# 01_fpga.net
KiCad netlist of a schematic drawn in Altium Designer
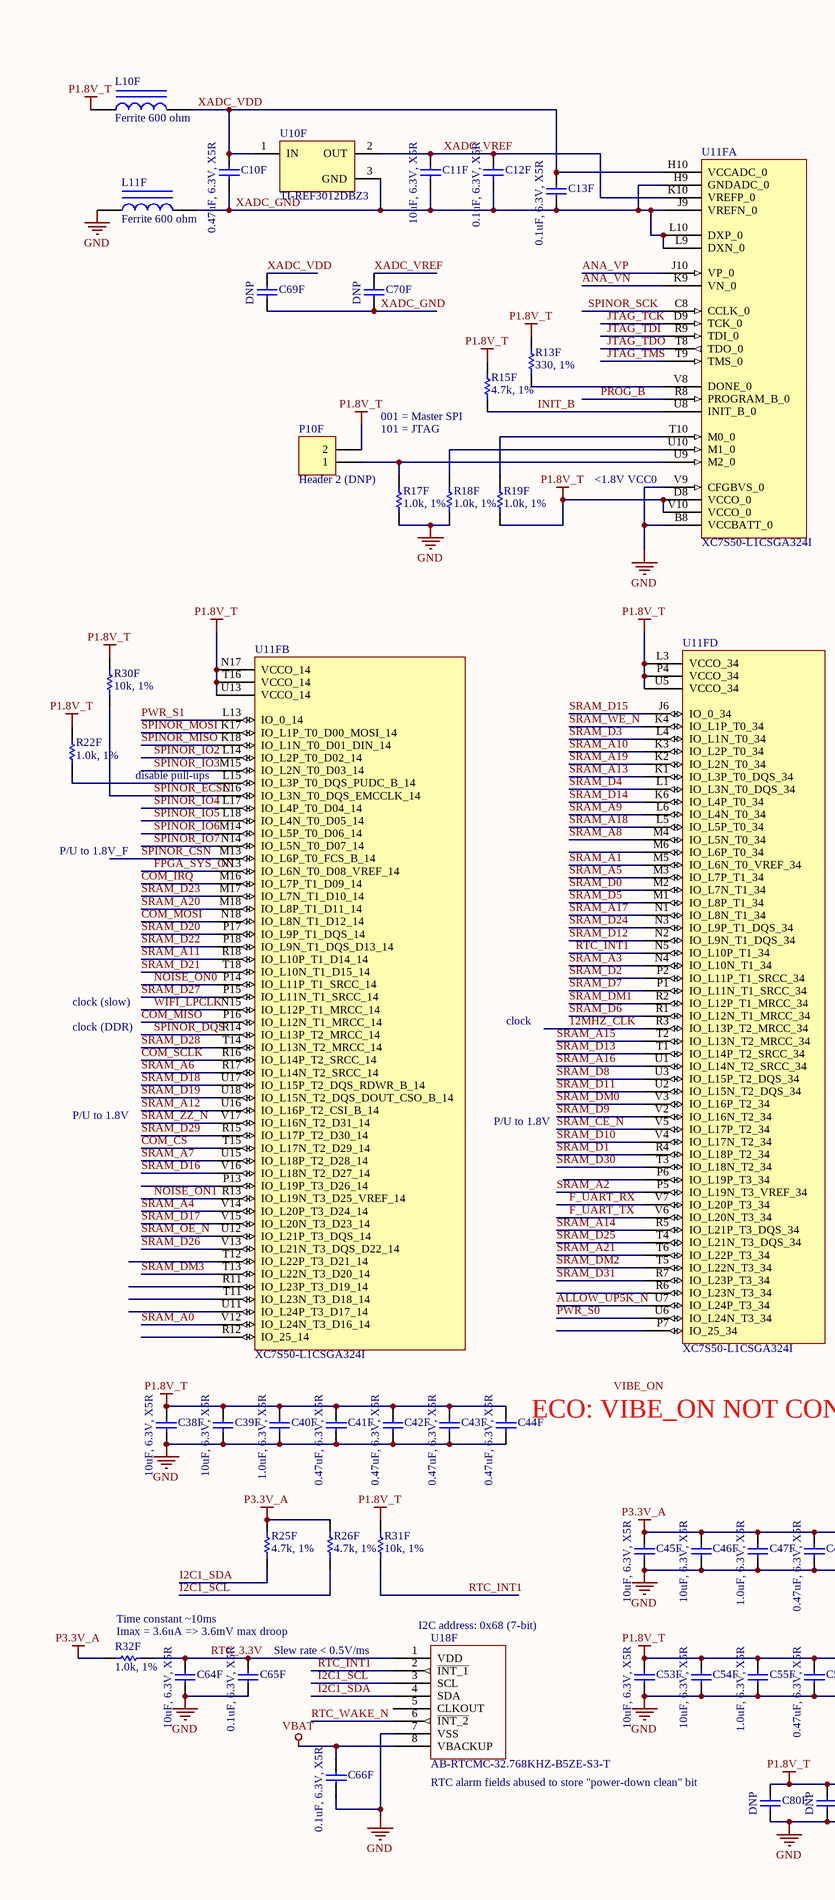
[diagram p0: 01_fpga.SchDoc, left]
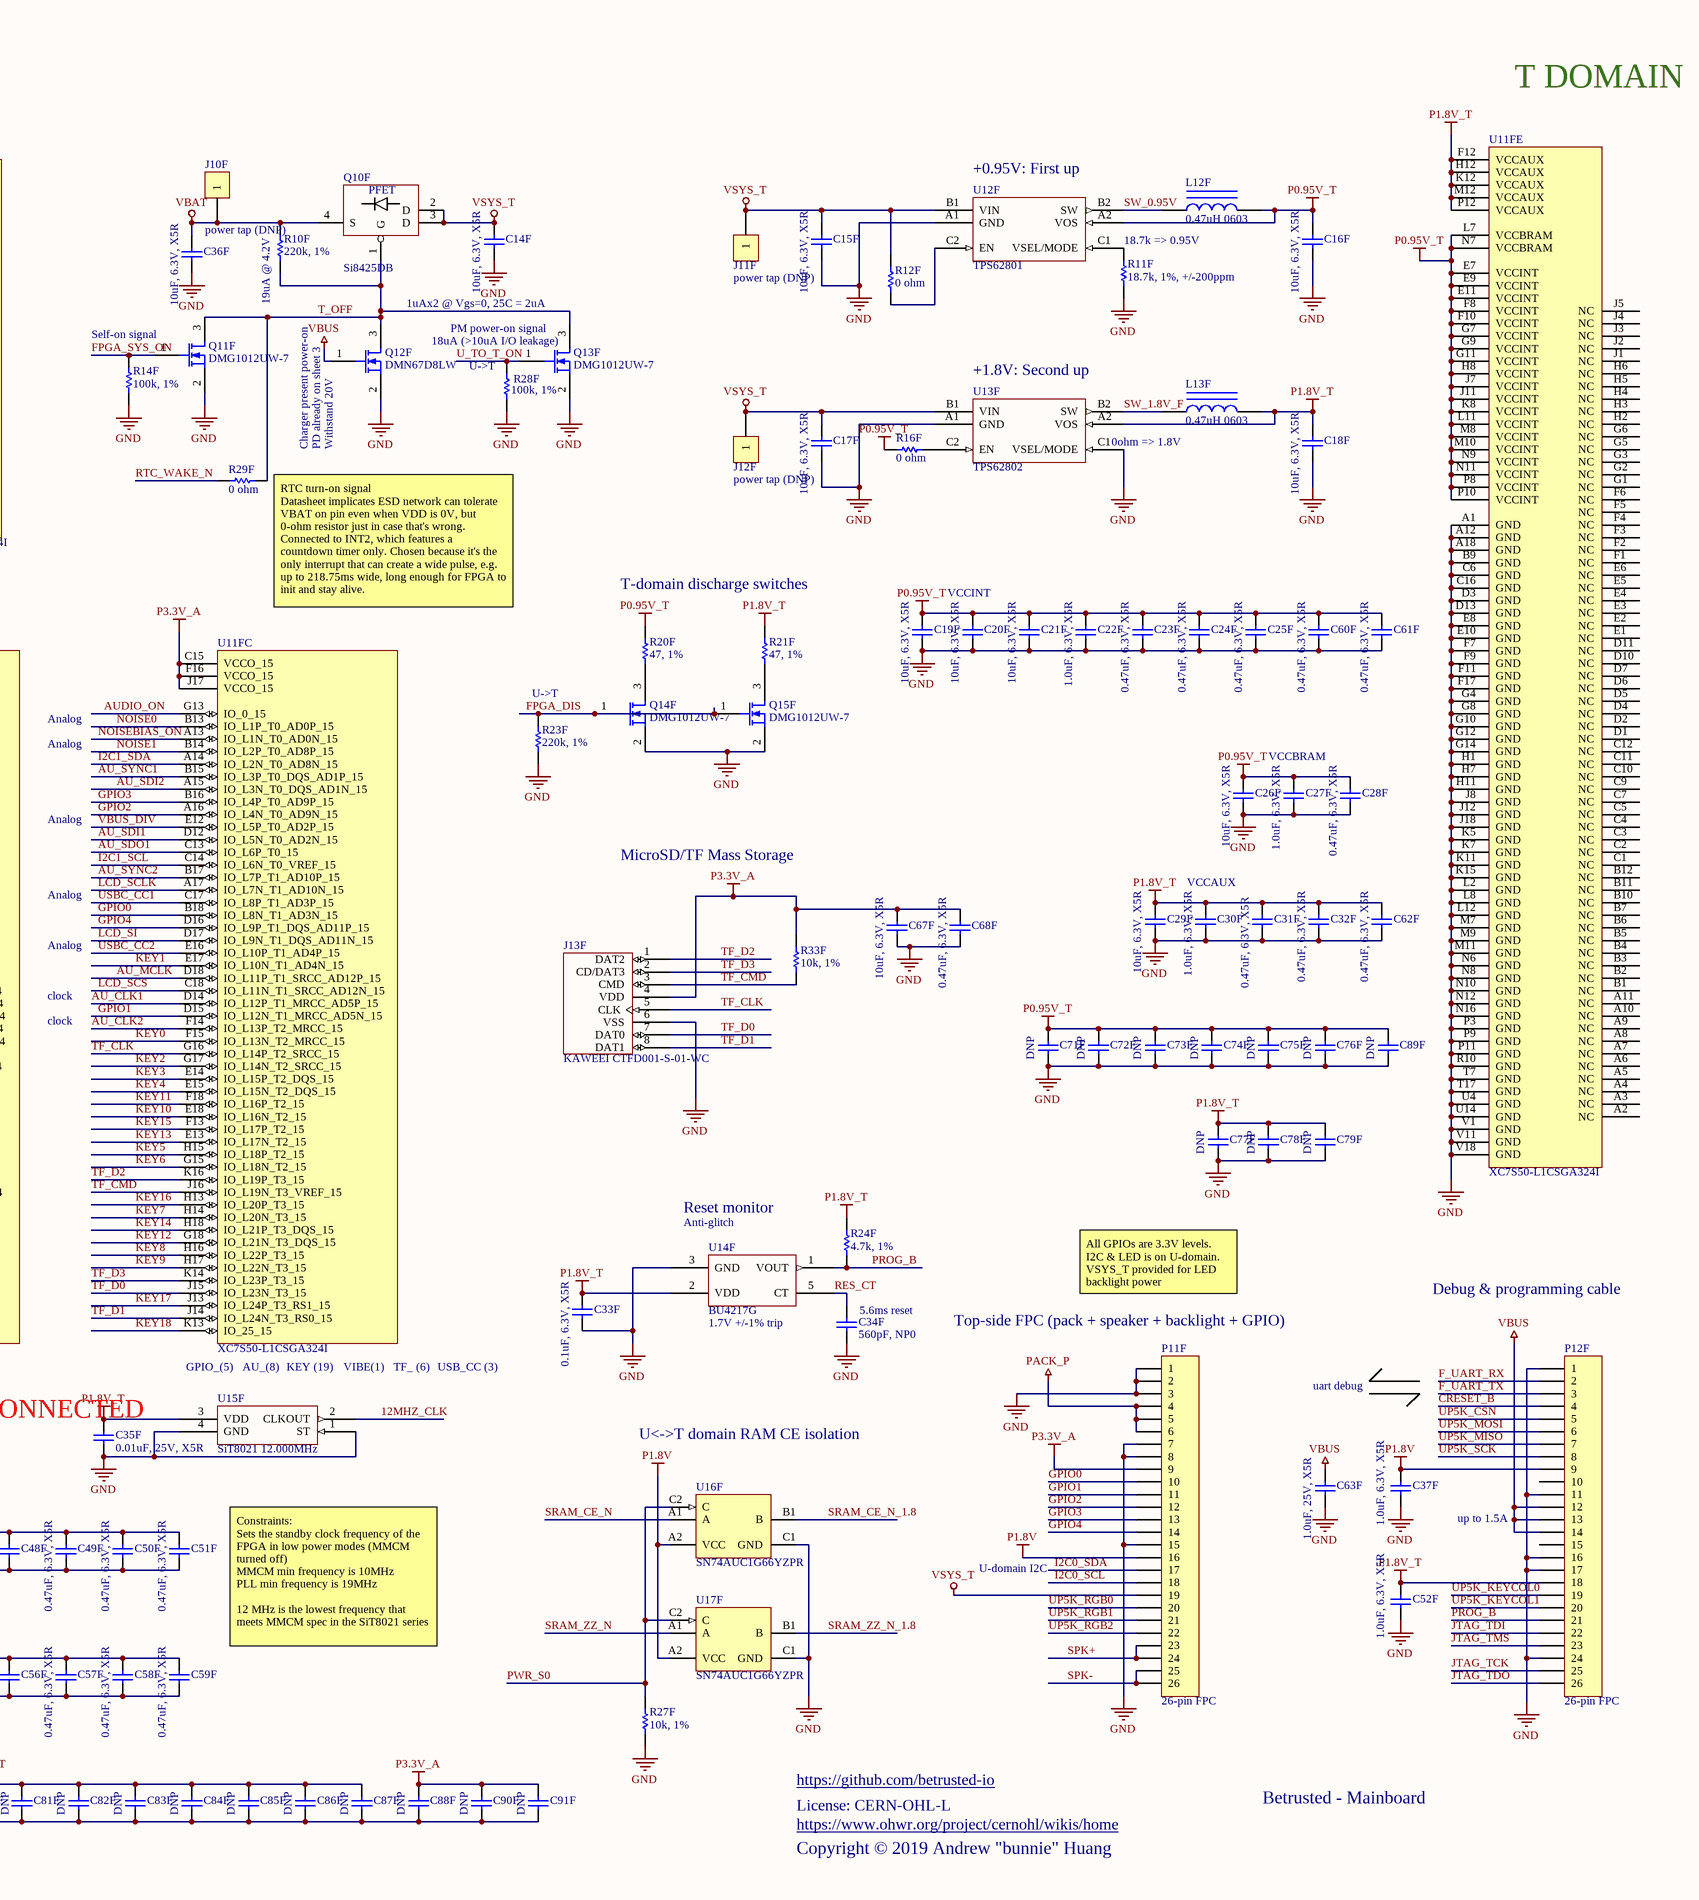
[diagram p1: 01_fpga.SchDoc, right]

(export (version "E")
  (design (tool "Eeschema 10.0.6"))
  (components
    (comp (ref "C10F")
      (value "0.47uF, 6.3V, X5R")
      (footprint "B_CAP0201")
      (description "Capacitor (Semiconductor SIM Model)")
      (fields (field (name "MPN") "CL03A474KQ3NNNH"))
      (libsource (lib "Miscellaneous Devices") (part "Cap Semi"))
    )
    (comp (ref "C11F")
      (value "10uF, 6.3V, X5R")
      (footprint "B_CAP0603")
      (description "Capacitor (Semiconductor SIM Model)")
      (fields (field (name "MPN") "CL10A106MQ8NNNC"))
      (libsource (lib "Miscellaneous Devices") (part "Cap Semi"))
    )
    (comp (ref "C12F")
      (value "0.1uF, 6.3V, X5R")
      (footprint "B_CAP0201")
      (description "Capacitor (Semiconductor SIM Model)")
      (fields (field (name "MPN") "CL03A104KQ3NNNC"))
      (libsource (lib "Miscellaneous Devices") (part "Cap Semi"))
    )
    (comp (ref "C13F")
      (value "0.1uF, 6.3V, X5R")
      (footprint "B_CAP0201")
      (description "Capacitor (Semiconductor SIM Model)")
      (fields (field (name "MPN") "CL03A104KQ3NNNC"))
      (libsource (lib "Miscellaneous Devices") (part "Cap Semi"))
    )
    (comp (ref "C14F")
      (value "10uF, 6.3V, X5R")
      (footprint "B_CAP0603")
      (description "Capacitor (Semiconductor SIM Model)")
      (fields (field (name "MPN") "CL10A106MQ8NNNC"))
      (libsource (lib "Miscellaneous Devices") (part "Cap Semi"))
    )
    (comp (ref "C15F")
      (value "10uF, 6.3V, X5R")
      (footprint "B_CAP0603")
      (description "Capacitor (Semiconductor SIM Model)")
      (fields (field (name "MPN") "CL10A106MQ8NNNC"))
      (libsource (lib "Miscellaneous Devices") (part "Cap Semi"))
    )
    (comp (ref "C16F")
      (value "10uF, 6.3V, X5R")
      (footprint "B_CAP0603")
      (description "Capacitor (Semiconductor SIM Model)")
      (fields (field (name "MPN") "CL10A106MQ8NNNC"))
      (libsource (lib "Miscellaneous Devices") (part "Cap Semi"))
    )
    (comp (ref "C17F")
      (value "10uF, 6.3V, X5R")
      (footprint "B_CAP0603")
      (description "Capacitor (Semiconductor SIM Model)")
      (fields (field (name "MPN") "CL10A106MQ8NNNC"))
      (libsource (lib "Miscellaneous Devices") (part "Cap Semi"))
    )
    (comp (ref "C18F")
      (value "10uF, 6.3V, X5R")
      (footprint "B_CAP0603")
      (description "Capacitor (Semiconductor SIM Model)")
      (fields (field (name "MPN") "CL10A106MQ8NNNC"))
      (libsource (lib "Miscellaneous Devices") (part "Cap Semi"))
    )
    (comp (ref "C19F")
      (value "10uF, 6.3V, X5R")
      (footprint "B_CAP0603")
      (description "Capacitor (Semiconductor SIM Model)")
      (fields (field (name "MPN") "CL10A106MQ8NNNC"))
      (libsource (lib "Miscellaneous Devices") (part "Cap Semi"))
    )
    (comp (ref "C20F")
      (value "10uF, 6.3V, X5R")
      (footprint "B_CAP0603")
      (description "Capacitor (Semiconductor SIM Model)")
      (fields (field (name "MPN") "CL10A106MQ8NNNC"))
      (libsource (lib "Miscellaneous Devices") (part "Cap Semi"))
    )
    (comp (ref "C21F")
      (value "10uF, 6.3V, X5R")
      (footprint "B_CAP0603")
      (description "Capacitor (Semiconductor SIM Model)")
      (fields (field (name "MPN") "CL10A106MQ8NNNC"))
      (libsource (lib "Miscellaneous Devices") (part "Cap Semi"))
    )
    (comp (ref "C22F")
      (value "1.0uF, 6.3V, X5R")
      (footprint "B_CAP0201")
      (description "Capacitor (Semiconductor SIM Model)")
      (fields (field (name "MPN") "GRM033R60J105MEA2D"))
      (libsource (lib "Miscellaneous Devices") (part "Cap Semi"))
    )
    (comp (ref "C23F")
      (value "0.47uF, 6.3V, X5R")
      (footprint "B_CAP0201")
      (description "Capacitor (Semiconductor SIM Model)")
      (fields (field (name "MPN") "CL03A474KQ3NNNH"))
      (libsource (lib "Miscellaneous Devices") (part "Cap Semi"))
    )
    (comp (ref "C24F")
      (value "0.47uF, 6.3V, X5R")
      (footprint "B_CAP0201")
      (description "Capacitor (Semiconductor SIM Model)")
      (fields (field (name "MPN") "CL03A474KQ3NNNH"))
      (libsource (lib "Miscellaneous Devices") (part "Cap Semi"))
    )
    (comp (ref "C25F")
      (value "0.47uF, 6.3V, X5R")
      (footprint "B_CAP0201")
      (description "Capacitor (Semiconductor SIM Model)")
      (fields (field (name "MPN") "CL03A474KQ3NNNH"))
      (libsource (lib "Miscellaneous Devices") (part "Cap Semi"))
    )
    (comp (ref "C26F")
      (value "10uF, 6.3V, X5R")
      (footprint "B_CAP0603")
      (description "Capacitor (Semiconductor SIM Model)")
      (fields (field (name "MPN") "CL10A106MQ8NNNC"))
      (libsource (lib "Miscellaneous Devices") (part "Cap Semi"))
    )
    (comp (ref "C27F")
      (value "1.0uF, 6.3V, X5R")
      (footprint "B_CAP0201")
      (description "Capacitor (Semiconductor SIM Model)")
      (fields (field (name "MPN") "GRM033R60J105MEA2D"))
      (libsource (lib "Miscellaneous Devices") (part "Cap Semi"))
    )
    (comp (ref "C28F")
      (value "0.47uF, 6.3V, X5R")
      (footprint "B_CAP0201")
      (description "Capacitor (Semiconductor SIM Model)")
      (fields (field (name "MPN") "CL03A474KQ3NNNH"))
      (libsource (lib "Miscellaneous Devices") (part "Cap Semi"))
    )
    (comp (ref "C29F")
      (value "10uF, 6.3V, X5R")
      (footprint "B_CAP0603")
      (description "Capacitor (Semiconductor SIM Model)")
      (fields (field (name "MPN") "CL10A106MQ8NNNC"))
      (libsource (lib "Miscellaneous Devices") (part "Cap Semi"))
    )
    (comp (ref "C30F")
      (value "1.0uF, 6.3V, X5R")
      (footprint "B_CAP0201")
      (description "Capacitor (Semiconductor SIM Model)")
      (fields (field (name "MPN") "GRM033R60J105MEA2D"))
      (libsource (lib "Miscellaneous Devices") (part "Cap Semi"))
    )
    (comp (ref "C31F")
      (value "0.47uF, 6.3V, X5R")
      (footprint "B_CAP0201")
      (description "Capacitor (Semiconductor SIM Model)")
      (fields (field (name "MPN") "CL03A474KQ3NNNH"))
      (libsource (lib "Miscellaneous Devices") (part "Cap Semi"))
    )
    (comp (ref "C32F")
      (value "0.47uF, 6.3V, X5R")
      (footprint "B_CAP0201")
      (description "Capacitor (Semiconductor SIM Model)")
      (fields (field (name "MPN") "CL03A474KQ3NNNH"))
      (libsource (lib "Miscellaneous Devices") (part "Cap Semi"))
    )
    (comp (ref "C33F")
      (value "0.1uF, 6.3V, X5R")
      (footprint "B_CAP0201")
      (description "Capacitor (Semiconductor SIM Model)")
      (fields (field (name "MPN") "CL03A104KQ3NNNC"))
      (libsource (lib "Miscellaneous Devices") (part "Cap Semi"))
    )
    (comp (ref "C34F")
      (value "560pF, NP0")
      (footprint "B_RES0201")
      (description "Capacitor (Semiconductor SIM Model)")
      (fields (field (name "MPN") "GRM0335C1E561JA01D"))
      (libsource (lib "Miscellaneous Devices") (part "Cap Semi"))
    )
    (comp (ref "C35F")
      (value "0.01uF, 25V, X5R")
      (footprint "B_RES0201")
      (description "Capacitor (Semiconductor SIM Model)")
      (fields (field (name "MPN") "GRM033R61E103KA12D"))
      (libsource (lib "Miscellaneous Devices") (part "Cap Semi"))
    )
    (comp (ref "C36F")
      (value "10uF, 6.3V, X5R")
      (footprint "B_CAP0603")
      (description "Capacitor (Semiconductor SIM Model)")
      (fields (field (name "MPN") "CL10A106MQ8NNNC"))
      (libsource (lib "Miscellaneous Devices") (part "Cap Semi"))
    )
    (comp (ref "C37F")
      (value "1.0uF, 6.3V, X5R")
      (footprint "B_CAP0201")
      (description "Capacitor (Semiconductor SIM Model)")
      (fields (field (name "MPN") "GRM033R60J105MEA2D"))
      (libsource (lib "Miscellaneous Devices") (part "Cap Semi"))
    )
    (comp (ref "C38F")
      (value "10uF, 6.3V, X5R")
      (footprint "B_CAP0603")
      (description "Capacitor (Semiconductor SIM Model)")
      (fields (field (name "MPN") "CL10A106MQ8NNNC"))
      (libsource (lib "Miscellaneous Devices") (part "Cap Semi"))
    )
    (comp (ref "C39F")
      (value "10uF, 6.3V, X5R")
      (footprint "B_CAP0603")
      (description "Capacitor (Semiconductor SIM Model)")
      (fields (field (name "MPN") "CL10A106MQ8NNNC"))
      (libsource (lib "Miscellaneous Devices") (part "Cap Semi"))
    )
    (comp (ref "C40F")
      (value "1.0uF, 6.3V, X5R")
      (footprint "B_CAP0201")
      (description "Capacitor (Semiconductor SIM Model)")
      (fields (field (name "MPN") "GRM033R60J105MEA2D"))
      (libsource (lib "Miscellaneous Devices") (part "Cap Semi"))
    )
    (comp (ref "C41F")
      (value "0.47uF, 6.3V, X5R")
      (footprint "B_CAP0201")
      (description "Capacitor (Semiconductor SIM Model)")
      (fields (field (name "MPN") "CL03A474KQ3NNNH"))
      (libsource (lib "Miscellaneous Devices") (part "Cap Semi"))
    )
    (comp (ref "C42F")
      (value "0.47uF, 6.3V, X5R")
      (footprint "B_CAP0201")
      (description "Capacitor (Semiconductor SIM Model)")
      (fields (field (name "MPN") "CL03A474KQ3NNNH"))
      (libsource (lib "Miscellaneous Devices") (part "Cap Semi"))
    )
    (comp (ref "C43F")
      (value "0.47uF, 6.3V, X5R")
      (footprint "B_CAP0201")
      (description "Capacitor (Semiconductor SIM Model)")
      (fields (field (name "MPN") "CL03A474KQ3NNNH"))
      (libsource (lib "Miscellaneous Devices") (part "Cap Semi"))
    )
    (comp (ref "C44F")
      (value "0.47uF, 6.3V, X5R")
      (footprint "B_CAP0201")
      (description "Capacitor (Semiconductor SIM Model)")
      (fields (field (name "MPN") "CL03A474KQ3NNNH"))
      (libsource (lib "Miscellaneous Devices") (part "Cap Semi"))
    )
    (comp (ref "C45F")
      (value "10uF, 6.3V, X5R")
      (footprint "B_CAP0603")
      (description "Capacitor (Semiconductor SIM Model)")
      (fields (field (name "MPN") "CL10A106MQ8NNNC"))
      (libsource (lib "Miscellaneous Devices") (part "Cap Semi"))
    )
    (comp (ref "C46F")
      (value "10uF, 6.3V, X5R")
      (footprint "B_CAP0603")
      (description "Capacitor (Semiconductor SIM Model)")
      (fields (field (name "MPN") "CL10A106MQ8NNNC"))
      (libsource (lib "Miscellaneous Devices") (part "Cap Semi"))
    )
    (comp (ref "C47F")
      (value "1.0uF, 6.3V, X5R")
      (footprint "B_CAP0201")
      (description "Capacitor (Semiconductor SIM Model)")
      (fields (field (name "MPN") "GRM033R60J105MEA2D"))
      (libsource (lib "Miscellaneous Devices") (part "Cap Semi"))
    )
    (comp (ref "C48F")
      (value "0.47uF, 6.3V, X5R")
      (footprint "B_CAP0201")
      (description "Capacitor (Semiconductor SIM Model)")
      (fields (field (name "MPN") "CL03A474KQ3NNNH"))
      (libsource (lib "Miscellaneous Devices") (part "Cap Semi"))
    )
    (comp (ref "C49F")
      (value "0.47uF, 6.3V, X5R")
      (footprint "B_CAP0201")
      (description "Capacitor (Semiconductor SIM Model)")
      (fields (field (name "MPN") "CL03A474KQ3NNNH"))
      (libsource (lib "Miscellaneous Devices") (part "Cap Semi"))
    )
    (comp (ref "C50F")
      (value "0.47uF, 6.3V, X5R")
      (footprint "B_CAP0201")
      (description "Capacitor (Semiconductor SIM Model)")
      (fields (field (name "MPN") "CL03A474KQ3NNNH"))
      (libsource (lib "Miscellaneous Devices") (part "Cap Semi"))
    )
    (comp (ref "C51F")
      (value "0.47uF, 6.3V, X5R")
      (footprint "B_CAP0201")
      (description "Capacitor (Semiconductor SIM Model)")
      (fields (field (name "MPN") "CL03A474KQ3NNNH"))
      (libsource (lib "Miscellaneous Devices") (part "Cap Semi"))
    )
    (comp (ref "C52F")
      (value "1.0uF, 6.3V, X5R")
      (footprint "B_CAP0201")
      (description "Capacitor (Semiconductor SIM Model)")
      (fields (field (name "MPN") "GRM033R60J105MEA2D"))
      (libsource (lib "Miscellaneous Devices") (part "Cap Semi"))
    )
    (comp (ref "C53F")
      (value "10uF, 6.3V, X5R")
      (footprint "B_CAP0603")
      (description "Capacitor (Semiconductor SIM Model)")
      (fields (field (name "MPN") "CL10A106MQ8NNNC"))
      (libsource (lib "Miscellaneous Devices") (part "Cap Semi"))
    )
    (comp (ref "C54F")
      (value "10uF, 6.3V, X5R")
      (footprint "B_CAP0603")
      (description "Capacitor (Semiconductor SIM Model)")
      (fields (field (name "MPN") "CL10A106MQ8NNNC"))
      (libsource (lib "Miscellaneous Devices") (part "Cap Semi"))
    )
    (comp (ref "C55F")
      (value "1.0uF, 6.3V, X5R")
      (footprint "B_CAP0201")
      (description "Capacitor (Semiconductor SIM Model)")
      (fields (field (name "MPN") "GRM033R60J105MEA2D"))
      (libsource (lib "Miscellaneous Devices") (part "Cap Semi"))
    )
    (comp (ref "C56F")
      (value "0.47uF, 6.3V, X5R")
      (footprint "B_CAP0201")
      (description "Capacitor (Semiconductor SIM Model)")
      (fields (field (name "MPN") "CL03A474KQ3NNNH"))
      (libsource (lib "Miscellaneous Devices") (part "Cap Semi"))
    )
    (comp (ref "C57F")
      (value "0.47uF, 6.3V, X5R")
      (footprint "B_CAP0201")
      (description "Capacitor (Semiconductor SIM Model)")
      (fields (field (name "MPN") "CL03A474KQ3NNNH"))
      (libsource (lib "Miscellaneous Devices") (part "Cap Semi"))
    )
    (comp (ref "C58F")
      (value "0.47uF, 6.3V, X5R")
      (footprint "B_CAP0201")
      (description "Capacitor (Semiconductor SIM Model)")
      (fields (field (name "MPN") "CL03A474KQ3NNNH"))
      (libsource (lib "Miscellaneous Devices") (part "Cap Semi"))
    )
    (comp (ref "C59F")
      (value "0.47uF, 6.3V, X5R")
      (footprint "B_CAP0201")
      (description "Capacitor (Semiconductor SIM Model)")
      (fields (field (name "MPN") "CL03A474KQ3NNNH"))
      (libsource (lib "Miscellaneous Devices") (part "Cap Semi"))
    )
    (comp (ref "C60F")
      (value "0.47uF, 6.3V, X5R")
      (footprint "B_CAP0201")
      (description "Capacitor (Semiconductor SIM Model)")
      (fields (field (name "MPN") "CL03A474KQ3NNNH"))
      (libsource (lib "Miscellaneous Devices") (part "Cap Semi"))
    )
    (comp (ref "C61F")
      (value "0.47uF, 6.3V, X5R")
      (footprint "B_CAP0201")
      (description "Capacitor (Semiconductor SIM Model)")
      (fields (field (name "MPN") "CL03A474KQ3NNNH"))
      (libsource (lib "Miscellaneous Devices") (part "Cap Semi"))
    )
    (comp (ref "C62F")
      (value "0.47uF, 6.3V, X5R")
      (footprint "B_CAP0201")
      (description "Capacitor (Semiconductor SIM Model)")
      (fields (field (name "MPN") "CL03A474KQ3NNNH"))
      (libsource (lib "Miscellaneous Devices") (part "Cap Semi"))
    )
    (comp (ref "C63F")
      (value "1.0uF, 25V, X5R")
      (footprint "B_CAP0603")
      (description "Capacitor (Semiconductor SIM Model)")
      (fields (field (name "MPN") "CL10A105KA8NNNC"))
      (libsource (lib "Miscellaneous Devices") (part "Cap Semi"))
    )
    (comp (ref "C64F")
      (value "10uF, 6.3V, X5R")
      (footprint "B_CAP0603")
      (description "Capacitor (Semiconductor SIM Model)")
      (fields (field (name "MPN") "CL10A106MQ8NNNC"))
      (libsource (lib "Miscellaneous Devices") (part "Cap Semi"))
    )
    (comp (ref "C65F")
      (value "0.1uF, 6.3V, X5R")
      (footprint "B_CAP0201")
      (description "Capacitor (Semiconductor SIM Model)")
      (fields (field (name "MPN") "CL03A104KQ3NNNC"))
      (libsource (lib "Miscellaneous Devices") (part "Cap Semi"))
    )
    (comp (ref "C66F")
      (value "0.1uF, 6.3V, X5R")
      (footprint "B_CAP0201")
      (description "Capacitor (Semiconductor SIM Model)")
      (fields (field (name "MPN") "CL03A104KQ3NNNC"))
      (libsource (lib "Miscellaneous Devices") (part "Cap Semi"))
    )
    (comp (ref "C67F")
      (value "10uF, 6.3V, X5R")
      (footprint "B_CAP0603")
      (description "Capacitor (Semiconductor SIM Model)")
      (fields (field (name "MPN") "CL10A106MQ8NNNC"))
      (libsource (lib "Miscellaneous Devices") (part "Cap Semi"))
    )
    (comp (ref "C68F")
      (value "0.47uF, 6.3V, X5R")
      (footprint "B_CAP0201")
      (description "Capacitor (Semiconductor SIM Model)")
      (fields (field (name "MPN") "CL03A474KQ3NNNH"))
      (libsource (lib "Miscellaneous Devices") (part "Cap Semi"))
    )
    (comp (ref "C69F")
      (value "DNP")
      (footprint "B_CAP0201")
      (description "Capacitor (Semiconductor SIM Model)")
      (libsource (lib "Miscellaneous Devices") (part "Cap Semi"))
    )
    (comp (ref "C70F")
      (value "DNP")
      (footprint "B_CAP0201")
      (description "Capacitor (Semiconductor SIM Model)")
      (libsource (lib "Miscellaneous Devices") (part "Cap Semi"))
    )
    (comp (ref "C71F")
      (value "DNP")
      (footprint "B_CAP0201")
      (description "Capacitor (Semiconductor SIM Model)")
      (libsource (lib "Miscellaneous Devices") (part "Cap Semi"))
    )
    (comp (ref "C72F")
      (value "DNP")
      (footprint "B_CAP0201")
      (description "Capacitor (Semiconductor SIM Model)")
      (libsource (lib "Miscellaneous Devices") (part "Cap Semi"))
    )
    (comp (ref "C73F")
      (value "DNP")
      (footprint "B_CAP0201")
      (description "Capacitor (Semiconductor SIM Model)")
      (libsource (lib "Miscellaneous Devices") (part "Cap Semi"))
    )
    (comp (ref "C74F")
      (value "DNP")
      (footprint "B_CAP0201")
      (description "Capacitor (Semiconductor SIM Model)")
      (libsource (lib "Miscellaneous Devices") (part "Cap Semi"))
    )
    (comp (ref "C75F")
      (value "DNP")
      (footprint "B_CAP0201")
      (description "Capacitor (Semiconductor SIM Model)")
      (libsource (lib "Miscellaneous Devices") (part "Cap Semi"))
    )
    (comp (ref "C76F")
      (value "DNP")
      (footprint "B_CAP0201")
      (description "Capacitor (Semiconductor SIM Model)")
      (libsource (lib "Miscellaneous Devices") (part "Cap Semi"))
    )
    (comp (ref "C77F")
      (value "DNP")
      (footprint "B_CAP0201")
      (description "Capacitor (Semiconductor SIM Model)")
      (libsource (lib "Miscellaneous Devices") (part "Cap Semi"))
    )
    (comp (ref "C78F")
      (value "DNP")
      (footprint "B_CAP0201")
      (description "Capacitor (Semiconductor SIM Model)")
      (libsource (lib "Miscellaneous Devices") (part "Cap Semi"))
    )
    (comp (ref "C79F")
      (value "DNP")
      (footprint "B_CAP0201")
      (description "Capacitor (Semiconductor SIM Model)")
      (libsource (lib "Miscellaneous Devices") (part "Cap Semi"))
    )
    (comp (ref "C80F")
      (value "DNP")
      (footprint "B_CAP0201")
      (description "Capacitor (Semiconductor SIM Model)")
      (libsource (lib "Miscellaneous Devices") (part "Cap Semi"))
    )
    (comp (ref "C81F")
      (value "DNP")
      (footprint "B_CAP0201")
      (description "Capacitor (Semiconductor SIM Model)")
      (libsource (lib "Miscellaneous Devices") (part "Cap Semi"))
    )
    (comp (ref "C82F")
      (value "DNP")
      (footprint "B_CAP0201")
      (description "Capacitor (Semiconductor SIM Model)")
      (libsource (lib "Miscellaneous Devices") (part "Cap Semi"))
    )
    (comp (ref "C83F")
      (value "DNP")
      (footprint "B_CAP0201")
      (description "Capacitor (Semiconductor SIM Model)")
      (libsource (lib "Miscellaneous Devices") (part "Cap Semi"))
    )
    (comp (ref "C84F")
      (value "DNP")
      (footprint "B_CAP0201")
      (description "Capacitor (Semiconductor SIM Model)")
      (libsource (lib "Miscellaneous Devices") (part "Cap Semi"))
    )
    (comp (ref "C85F")
      (value "DNP")
      (footprint "B_CAP0201")
      (description "Capacitor (Semiconductor SIM Model)")
      (libsource (lib "Miscellaneous Devices") (part "Cap Semi"))
    )
    (comp (ref "C86F")
      (value "DNP")
      (footprint "B_CAP0201")
      (description "Capacitor (Semiconductor SIM Model)")
      (libsource (lib "Miscellaneous Devices") (part "Cap Semi"))
    )
    (comp (ref "C87F")
      (value "DNP")
      (footprint "B_CAP0201")
      (description "Capacitor (Semiconductor SIM Model)")
      (libsource (lib "Miscellaneous Devices") (part "Cap Semi"))
    )
    (comp (ref "C88F")
      (value "DNP")
      (footprint "B_CAP0201")
      (description "Capacitor (Semiconductor SIM Model)")
      (libsource (lib "Miscellaneous Devices") (part "Cap Semi"))
    )
    (comp (ref "C89F")
      (value "DNP")
      (footprint "B_CAP0201")
      (description "Capacitor (Semiconductor SIM Model)")
      (libsource (lib "Miscellaneous Devices") (part "Cap Semi"))
    )
    (comp (ref "C90F")
      (value "DNP")
      (footprint "B_CAP0201")
      (description "Capacitor (Semiconductor SIM Model)")
      (libsource (lib "Miscellaneous Devices") (part "Cap Semi"))
    )
    (comp (ref "C91F")
      (value "DNP")
      (footprint "B_CAP0201")
      (description "Capacitor (Semiconductor SIM Model)")
      (libsource (lib "Miscellaneous Devices") (part "Cap Semi"))
    )
    (comp (ref "J10F")
      (value "power tap (DNP)")
      (footprint "RESTAP-0603")
      (description "Connector")
      (fields (field (name "MPN") "DNP"))
      (libsource (lib "") (part "CON1_1"))
    )
    (comp (ref "J11F")
      (value "power tap (DNP)")
      (footprint "RESTAP-0603")
      (description "Connector")
      (fields (field (name "MPN") "DNP"))
      (libsource (lib "*") (part "CON1"))
    )
    (comp (ref "J12F")
      (value "power tap (DNP)")
      (footprint "RESTAP-0603")
      (description "Connector")
      (fields (field (name "MPN") "DNP"))
      (libsource (lib "*") (part "CON1"))
    )
    (comp (ref "J13F")
      (value "KAWEEI CTFD001-S-01-WC")
      (footprint "AUK_TFC08W01-HC-H")
      (description "Captive Micro-SD card for firmware images")
      (fields (field (name "MPN") "0472192001"))
      (libsource (lib "commonsch") (part "MICRO_SD"))
    )
    (comp (ref "L10F")
      (value "Ferrite 600 ohm")
      (footprint "B_IND0603")
      (description "Magnetic-Core Inductor")
      (fields (field (name "MPN") "BLM18AG601SN1D"))
      (libsource (lib "Miscellaneous Devices") (part "Inductor Iron"))
    )
    (comp (ref "L11F")
      (value "Ferrite 600 ohm")
      (footprint "B_IND0603")
      (description "Magnetic-Core Inductor")
      (fields (field (name "MPN") "BLM18AG601SN1D"))
      (libsource (lib "Miscellaneous Devices") (part "Inductor Iron"))
    )
    (comp (ref "L12F")
      (value "0.47uH 0603")
      (footprint "B_IND0603")
      (description "Magnetic-Core Inductor")
      (fields (field (name "MPN") "TFM160808ALC-R47MTAA"))
      (libsource (lib "Miscellaneous Devices") (part "Inductor Iron"))
    )
    (comp (ref "L13F")
      (value "0.47uH 0603")
      (footprint "B_IND0603")
      (description "Magnetic-Core Inductor")
      (fields (field (name "MPN") "TFM160808ALC-R47MTAA"))
      (libsource (lib "Miscellaneous Devices") (part "Inductor Iron"))
    )
    (comp (ref "P10F")
      (value "Header 2 (DNP)")
      (footprint "HDR1X2")
      (description "Header, 2-Pin, 2.54mm")
      (fields (field (name "MPN") "DNP") (field (name "PUBLISHER") "Altium Limited"))
      (libsource (lib "Miscellaneous Connectors") (part "Header 2"))
    )
    (comp (ref "P11F")
      (value "26-pin FPC")
      (footprint "HRS_FH34SRJ-26S-0.5SH(50)")
      (description "26 Pin FPC header")
      (fields (field (name "MPN") "FH34SRJ-26S-0.5SH(99)"))
      (libsource (lib "commonsch-new") (part "FPC-26"))
    )
    (comp (ref "P12F")
      (value "26-pin FPC")
      (footprint "HRS_FH34SRJ-26S-0.5SH(50)")
      (description "26 Pin FPC header")
      (fields (field (name "MPN") "FH34SRJ-26S-0.5SH(99)"))
      (libsource (lib "commonsch-new") (part "FPC-26"))
    )
    (comp (ref "Q10F")
      (value "Si8425DB")
      (footprint "VISHAY_MICRO_FOOT_4_BUMP")
      (description "P-channel 20V 6.2A 27mOhm @ -2.5V")
      (fields (field (name "MPN") "SI8457DB-T1-E1"))
      (libsource (lib "temp-to-merge") (part "Si8425DB"))
    )
    (comp (ref "Q11F")
      (value "DMG1012UW-7")
      (footprint "SOT323-3AN")
      (description "N-Channel MOSFET")
      (fields (field (name "PUBLISHER") "Altium Limited"))
      (libsource (lib "Miscellaneous Devices") (part "MOSFET-N"))
    )
    (comp (ref "Q12F")
      (value "DMN67D8LW")
      (footprint "SOT323-3AN")
      (description "N-Channel MOSFET")
      (fields (field (name "PUBLISHER") "Altium Limited"))
      (libsource (lib "Miscellaneous Devices") (part "MOSFET-N"))
    )
    (comp (ref "Q13F")
      (value "DMG1012UW-7")
      (footprint "SOT323-3AN")
      (description "N-Channel MOSFET")
      (fields (field (name "PUBLISHER") "Altium Limited"))
      (libsource (lib "Miscellaneous Devices") (part "MOSFET-N"))
    )
    (comp (ref "Q14F")
      (value "DMG1012UW-7")
      (footprint "SOT323-3AN")
      (description "N-Channel MOSFET")
      (fields (field (name "PUBLISHER") "Altium Limited"))
      (libsource (lib "Miscellaneous Devices") (part "MOSFET-N"))
    )
    (comp (ref "Q15F")
      (value "DMG1012UW-7")
      (footprint "SOT323-3AN")
      (description "N-Channel MOSFET")
      (fields (field (name "PUBLISHER") "Altium Limited"))
      (libsource (lib "Miscellaneous Devices") (part "MOSFET-N"))
    )
    (comp (ref "R10F")
      (value "220k, 1%")
      (footprint "B_RES0201")
      (description "Resistor")
      (fields (field (name "MPN") "ANY"))
      (libsource (lib "Miscellaneous Devices") (part "Res1"))
    )
    (comp (ref "R11F")
      (value "18.7k, 1%, +/-200ppm")
      (footprint "B_RES0402")
      (description "Resistor")
      (fields (field (name "MPN") "RC0402FR-0718K7L"))
      (libsource (lib "Miscellaneous Devices") (part "Res1"))
    )
    (comp (ref "R12F")
      (value "0 ohm")
      (footprint "B_RES0201")
      (description "Resistor")
      (fields (field (name "MPN") "ANY"))
      (libsource (lib "Miscellaneous Devices") (part "Res1"))
    )
    (comp (ref "R13F")
      (value "330, 1%")
      (footprint "B_RES0201")
      (description "Resistor")
      (fields (field (name "MPN") "ANY"))
      (libsource (lib "Miscellaneous Devices") (part "Res1"))
    )
    (comp (ref "R14F")
      (value "100k, 1%")
      (footprint "B_RES0201")
      (description "Resistor")
      (fields (field (name "MPN") "ANY"))
      (libsource (lib "Miscellaneous Devices") (part "Res1"))
    )
    (comp (ref "R15F")
      (value "4.7k, 1%")
      (footprint "B_RES0201")
      (description "Resistor")
      (fields (field (name "MPN") "ANY"))
      (libsource (lib "Miscellaneous Devices") (part "Res1"))
    )
    (comp (ref "R16F")
      (value "0 ohm")
      (footprint "B_RES0201")
      (description "Resistor")
      (fields (field (name "MPN") "ANY"))
      (libsource (lib "Miscellaneous Devices") (part "Res1"))
    )
    (comp (ref "R17F")
      (value "1.0k, 1%")
      (footprint "B_RES0201")
      (description "Resistor")
      (fields (field (name "MPN") "ANY"))
      (libsource (lib "Miscellaneous Devices") (part "Res1"))
    )
    (comp (ref "R18F")
      (value "1.0k, 1%")
      (footprint "B_RES0201")
      (description "Resistor")
      (fields (field (name "MPN") "ANY"))
      (libsource (lib "Miscellaneous Devices") (part "Res1"))
    )
    (comp (ref "R19F")
      (value "1.0k, 1%")
      (footprint "B_RES0201")
      (description "Resistor")
      (fields (field (name "MPN") "ANY"))
      (libsource (lib "Miscellaneous Devices") (part "Res1"))
    )
    (comp (ref "R20F")
      (value "47, 1%")
      (footprint "B_RES0402")
      (description "Resistor")
      (fields (field (name "MPN") "ANY"))
      (libsource (lib "Miscellaneous Devices") (part "Res1"))
    )
    (comp (ref "R21F")
      (value "47, 1%")
      (footprint "B_RES0402")
      (description "Resistor")
      (fields (field (name "MPN") "ANY"))
      (libsource (lib "Miscellaneous Devices") (part "Res1"))
    )
    (comp (ref "R22F")
      (value "1.0k, 1%")
      (footprint "B_RES0201")
      (description "Resistor")
      (fields (field (name "MPN") "ANY"))
      (libsource (lib "Miscellaneous Devices") (part "Res1"))
    )
    (comp (ref "R23F")
      (value "220k, 1%")
      (footprint "B_RES0201")
      (description "Resistor")
      (fields (field (name "MPN") "ANY"))
      (libsource (lib "Miscellaneous Devices") (part "Res1"))
    )
    (comp (ref "R24F")
      (value "4.7k, 1%")
      (footprint "B_RES0201")
      (description "Resistor")
      (fields (field (name "MPN") "ANY"))
      (libsource (lib "Miscellaneous Devices") (part "Res1"))
    )
    (comp (ref "R25F")
      (value "4.7k, 1%")
      (footprint "B_RES0201")
      (description "Resistor")
      (fields (field (name "MPN") "ANY"))
      (libsource (lib "Miscellaneous Devices") (part "Res1"))
    )
    (comp (ref "R26F")
      (value "4.7k, 1%")
      (footprint "B_RES0201")
      (description "Resistor")
      (fields (field (name "MPN") "ANY"))
      (libsource (lib "Miscellaneous Devices") (part "Res1"))
    )
    (comp (ref "R27F")
      (value "10k, 1%")
      (footprint "B_RES0201")
      (description "Resistor")
      (fields (field (name "MPN") "ANY"))
      (libsource (lib "Miscellaneous Devices") (part "Res1"))
    )
    (comp (ref "R28F")
      (value "100k, 1%")
      (footprint "B_RES0201")
      (description "Resistor")
      (fields (field (name "MPN") "ANY"))
      (libsource (lib "Miscellaneous Devices") (part "Res1"))
    )
    (comp (ref "R29F")
      (value "0 ohm")
      (footprint "B_RES0201")
      (description "Resistor")
      (fields (field (name "MPN") "ANY"))
      (libsource (lib "Miscellaneous Devices") (part "Res1"))
    )
    (comp (ref "R30F")
      (value "10k, 1%")
      (footprint "B_RES0201")
      (description "Resistor")
      (fields (field (name "MPN") "ANY"))
      (libsource (lib "Miscellaneous Devices") (part "Res1"))
    )
    (comp (ref "R31F")
      (value "10k, 1%")
      (footprint "B_RES0201")
      (description "Resistor")
      (fields (field (name "MPN") "ANY"))
      (libsource (lib "Miscellaneous Devices") (part "Res1"))
    )
    (comp (ref "R32F")
      (value "1.0k, 1%")
      (footprint "B_RES0201")
      (description "Resistor")
      (fields (field (name "MPN") "ANY"))
      (libsource (lib "Miscellaneous Devices") (part "Res1"))
    )
    (comp (ref "R33F")
      (value "10k, 1%")
      (footprint "B_RES0201")
      (description "Resistor")
      (fields (field (name "MPN") "ANY"))
      (libsource (lib "Miscellaneous Devices") (part "Res1"))
    )
    (comp (ref "U10F")
      (value "TI-REF3012DBZ3")
      (footprint "ONSC-SOT-23-3-318-08_V")
      (fields (field (name "MPN") "REF3012AIDBZT"))
      (libsource (lib "TI-REF3012DBZ3") (part "TI-REF3012DBZ3"))
    )
    (comp (ref "U11F")
      (value "XC7S50-L1CSGA324I")
      (footprint "BGA324C80P18X18_1500X1500X150")
      (description "Spartan 7 FPGA in CSGA324 package")
      (libsource (lib "commonsch-new") (part "XC7S25CSGA324"))
    )
    (comp (ref "U12F")
      (value "TPS62801")
      (footprint "BGA6C35P2X3_70X105X40_NSMD")
      (description "Buck regulator, 4MHz, 0.6A, 0.8V-1.55V, low Iq")
      (fields (field (name "MPN") "TPS62801YKAT"))
      (libsource (lib "altium-import") (part "root_0_TPS62801_"))
    )
    (comp (ref "U13F")
      (value "TPS62802")
      (footprint "BGA6C35P2X3_70X105X40_NSMD")
      (description "Buck regulator, 4MHz, 0.6A, 1.8V-3.3V, low Iq")
      (fields (field (name "MPN") "TPS62802YKAR"))
      (libsource (lib "altium-import") (part "root_0_TPS62802_"))
    )
    (comp (ref "U14F")
      (value "BU4217G")
      (footprint "SOT23-5AN")
      (description "Low voltage free delay time setting CMOS voltage detector IC")
      (fields (field (name "MPN") "BU4217G-TR"))
      (libsource (lib "commonsch-new") (part "BU42XXG"))
    )
    (comp (ref "U15F")
      (value "SiT8021 12.000MHz")
      (footprint "SiTIME_CSP")
      (description "1 to 26 MHz micropower oscillator")
      (fields (field (name "MPN") "SIT8021AI-J4-18S-12.000000E"))
      (libsource (lib "altium-import") (part "root_2_SiT8021_"))
    )
    (comp (ref "U16F")
      (value "SN74AUC1G66YZPR")
      (footprint "YZP0005ADAD")
      (description "Single Bilateral Analog Switch, YZP0005ADAD, LARGE T&R")
      (fields
        (field (name "MANUFACTURER") "Texas Instruments")
        (field (name "GENERIC PART NUMBER") "SN74AUC1G66")
      )
      (libsource (lib "Components - 04.06.19 - 14.52") (part "CMP-0859-01029-3"))
    )
    (comp (ref "U17F")
      (value "SN74AUC1G66YZPR")
      (footprint "YZP0005ADAD")
      (description "Single Bilateral Analog Switch, YZP0005ADAD, LARGE T&R")
      (fields
        (field (name "MANUFACTURER") "Texas Instruments")
        (field (name "GENERIC PART NUMBER") "SN74AUC1G66")
      )
      (libsource (lib "Components - 04.06.19 - 14.52") (part "CMP-0859-01029-3"))
    )
    (comp (ref "U18F")
      (value "AB-RTCMC-32.768KHZ-B5ZE-S3-T")
      (footprint "ABRACON_RTCMC_LGA10")
      (description "RTC Module with I2C Bus")
      (libsource (lib "commonsch-new") (part "AB-RTCMC-32.768kHZ-B5ZE-S3"))
    )
  )
  (nets
    (net (code "1") (name "/12MHZ_CLK") (class "Default")
      (node (ref "U11F") (pin "R3") (pinfunction "IO_L13P_T2_MRCC_34_R3") (pintype "bidirectional"))
      (node (ref "U15F") (pin "2") (pinfunction "CLKOUT_2") (pintype "output"))
    )
    (net (code "2") (name "/ALLOW_UP5K_N") (class "Default")
      (node (ref "U11F") (pin "U7") (pinfunction "IO_L24P_T3_34_U7") (pintype "bidirectional"))
    )
    (net (code "3") (name "/ANA_VN") (class "Default")
      (node (ref "U11F") (pin "K9") (pinfunction "VN_0_K9") (pintype "passive"))
    )
    (net (code "4") (name "/ANA_VP") (class "Default")
      (node (ref "U11F") (pin "J10") (pinfunction "VP_0_J10") (pintype "input"))
    )
    (net (code "5") (name "/AUDIO_ON") (class "Default")
      (node (ref "U11F") (pin "G13") (pinfunction "IO_0_15_G13") (pintype "bidirectional"))
    )
    (net (code "6") (name "/AU_CLK1") (class "Default")
      (node (ref "U11F") (pin "D14") (pinfunction "IO_L12P_T1_MRCC_AD5P_15_D14") (pintype "bidirectional"))
    )
    (net (code "7") (name "/AU_CLK2") (class "Default")
      (node (ref "U11F") (pin "F14") (pinfunction "IO_L13P_T2_MRCC_15_F14") (pintype "bidirectional"))
    )
    (net (code "8") (name "/AU_MCLK") (class "Default")
      (node (ref "U11F") (pin "D18") (pinfunction "IO_L11P_T1_SRCC_AD12P_15_D18") (pintype "bidirectional"))
    )
    (net (code "9") (name "/AU_SDI1") (class "Default")
      (node (ref "U11F") (pin "D12") (pinfunction "IO_L5N_T0_AD2N_15_D12") (pintype "bidirectional"))
    )
    (net (code "10") (name "/AU_SDI2") (class "Default")
      (node (ref "U11F") (pin "A15") (pinfunction "IO_L3N_T0_DQS_AD1N_15_A15") (pintype "bidirectional"))
    )
    (net (code "11") (name "/AU_SDO1") (class "Default")
      (node (ref "U11F") (pin "C13") (pinfunction "IO_L6P_T0_15_C13") (pintype "bidirectional"))
    )
    (net (code "12") (name "/AU_SYNC1") (class "Default")
      (node (ref "U11F") (pin "B15") (pinfunction "IO_L3P_T0_DQS_AD1P_15_B15") (pintype "bidirectional"))
    )
    (net (code "13") (name "/AU_SYNC2") (class "Default")
      (node (ref "U11F") (pin "B17") (pinfunction "IO_L7P_T1_AD10P_15_B17") (pintype "bidirectional"))
    )
    (net (code "14") (name "/COM_CS") (class "Default")
      (node (ref "U11F") (pin "T15") (pinfunction "IO_L17N_T2_D29_14_T15") (pintype "bidirectional"))
    )
    (net (code "15") (name "/COM_IRQ") (class "Default")
      (node (ref "U11F") (pin "M16") (pinfunction "IO_L7P_T1_D09_14_M16") (pintype "bidirectional"))
    )
    (net (code "16") (name "/COM_MISO") (class "Default")
      (node (ref "U11F") (pin "P16") (pinfunction "IO_L12N_T1_MRCC_14_P16") (pintype "bidirectional"))
    )
    (net (code "17") (name "/COM_MOSI") (class "Default")
      (node (ref "U11F") (pin "N18") (pinfunction "IO_L8N_T1_D12_14_N18") (pintype "bidirectional"))
    )
    (net (code "18") (name "/COM_SCLK") (class "Default")
      (node (ref "U11F") (pin "R16") (pinfunction "IO_L14P_T2_SRCC_14_R16") (pintype "bidirectional"))
    )
    (net (code "19") (name "/CRESET_B") (class "Default")
      (node (ref "P12F") (pin "4") (pinfunction "4_4") (pintype "passive"))
    )
    (net (code "20") (name "/FPGA_DIS") (class "Default")
      (node (ref "Q14F") (pin "1") (pinfunction "G_1") (pintype "passive"))
      (node (ref "Q15F") (pin "1") (pinfunction "G_1") (pintype "passive"))
      (node (ref "R23F") (pin "2") (pinfunction "2_2") (pintype "passive"))
    )
    (net (code "21") (name "/FPGA_SYS_ON") (class "Default")
      (node (ref "Q11F") (pin "1") (pinfunction "G_1") (pintype "passive"))
      (node (ref "R14F") (pin "2") (pinfunction "2_2") (pintype "passive"))
      (node (ref "U11F") (pin "N13") (pinfunction "IO_L6N_T0_D08_VREF_14_N13") (pintype "bidirectional"))
    )
    (net (code "22") (name "/F_UART_RX") (class "Default")
      (node (ref "P12F") (pin "2") (pinfunction "2_2") (pintype "passive"))
      (node (ref "U11F") (pin "V7") (pinfunction "IO_L20P_T3_34_V7") (pintype "bidirectional"))
    )
    (net (code "23") (name "/F_UART_TX") (class "Default")
      (node (ref "P12F") (pin "3") (pinfunction "3_3") (pintype "passive"))
      (node (ref "U11F") (pin "V6") (pinfunction "IO_L20N_T3_34_V6") (pintype "bidirectional"))
    )
    (net (code "24") (name "/GPIO0") (class "Default")
      (node (ref "P11F") (pin "10") (pinfunction "10_10") (pintype "passive"))
      (node (ref "U11F") (pin "B18") (pinfunction "IO_L8N_T1_AD3N_15_B18") (pintype "bidirectional"))
    )
    (net (code "25") (name "/GPIO1") (class "Default")
      (node (ref "P11F") (pin "11") (pinfunction "11_11") (pintype "passive"))
      (node (ref "U11F") (pin "D15") (pinfunction "IO_L12N_T1_MRCC_AD5N_15_D15") (pintype "bidirectional"))
    )
    (net (code "26") (name "/GPIO2") (class "Default")
      (node (ref "P11F") (pin "12") (pinfunction "12_12") (pintype "passive"))
      (node (ref "U11F") (pin "A16") (pinfunction "IO_L4N_T0_AD9N_15_A16") (pintype "bidirectional"))
    )
    (net (code "27") (name "/GPIO3") (class "Default")
      (node (ref "P11F") (pin "13") (pinfunction "13_13") (pintype "passive"))
      (node (ref "U11F") (pin "B16") (pinfunction "IO_L4P_T0_AD9P_15_B16") (pintype "bidirectional"))
    )
    (net (code "28") (name "/GPIO4") (class "Default")
      (node (ref "P11F") (pin "14") (pinfunction "14_14") (pintype "passive"))
      (node (ref "U11F") (pin "D16") (pinfunction "IO_L9P_T1_DQS_AD11P_15_D16") (pintype "bidirectional"))
    )
    (net (code "29") (name "/I2C0_SCL") (class "Default")
      (node (ref "P11F") (pin "18") (pinfunction "18_18") (pintype "passive"))
    )
    (net (code "30") (name "/I2C0_SDA") (class "Default")
      (node (ref "P11F") (pin "17") (pinfunction "17_17") (pintype "passive"))
    )
    (net (code "31") (name "/I2C1_SCL") (class "Default")
      (node (ref "R26F") (pin "1") (pinfunction "1_1") (pintype "passive"))
      (node (ref "U11F") (pin "C14") (pinfunction "IO_L6N_T0_VREF_15_C14") (pintype "bidirectional"))
      (node (ref "U18F") (pin "3") (pinfunction "SCL_3") (pintype "open_collector"))
    )
    (net (code "32") (name "/I2C1_SDA") (class "Default")
      (node (ref "R25F") (pin "1") (pinfunction "1_1") (pintype "passive"))
      (node (ref "U11F") (pin "A14") (pinfunction "IO_L2N_T0_AD8N_15_A14") (pintype "bidirectional"))
      (node (ref "U18F") (pin "4") (pinfunction "SDA_4") (pintype "open_collector"))
    )
    (net (code "33") (name "/INIT_B") (class "Default")
      (node (ref "R15F") (pin "1") (pinfunction "1_1") (pintype "passive"))
      (node (ref "U11F") (pin "U8") (pinfunction "INIT_B_0_U8") (pintype "open_collector"))
    )
    (net (code "34") (name "/JTAG_TCK") (class "Default")
      (node (ref "P12F") (pin "25") (pinfunction "25_25") (pintype "passive"))
      (node (ref "U11F") (pin "D9") (pinfunction "TCK_0_D9") (pintype "input"))
    )
    (net (code "35") (name "/JTAG_TDI") (class "Default")
      (node (ref "P12F") (pin "22") (pinfunction "22_22") (pintype "passive"))
      (node (ref "U11F") (pin "R9") (pinfunction "TDI_0_R9") (pintype "input"))
    )
    (net (code "36") (name "/JTAG_TDO") (class "Default")
      (node (ref "P12F") (pin "26") (pinfunction "26_26") (pintype "passive"))
      (node (ref "U11F") (pin "T8") (pinfunction "TDO_0_T8") (pintype "output"))
    )
    (net (code "37") (name "/JTAG_TMS") (class "Default")
      (node (ref "P12F") (pin "23") (pinfunction "23_23") (pintype "passive"))
      (node (ref "U11F") (pin "T9") (pinfunction "TMS_0_T9") (pintype "input"))
    )
    (net (code "38") (name "/KEY0") (class "Default")
      (node (ref "U11F") (pin "F15") (pinfunction "IO_L13N_T2_MRCC_15_F15") (pintype "bidirectional"))
    )
    (net (code "39") (name "/KEY1") (class "Default")
      (node (ref "U11F") (pin "E17") (pinfunction "IO_L10N_T1_AD4N_15_E17") (pintype "bidirectional"))
    )
    (net (code "40") (name "/KEY2") (class "Default")
      (node (ref "U11F") (pin "G17") (pinfunction "IO_L14N_T2_SRCC_15_G17") (pintype "bidirectional"))
    )
    (net (code "41") (name "/KEY3") (class "Default")
      (node (ref "U11F") (pin "E14") (pinfunction "IO_L15P_T2_DQS_15_E14") (pintype "bidirectional"))
    )
    (net (code "42") (name "/KEY4") (class "Default")
      (node (ref "U11F") (pin "E15") (pinfunction "IO_L15N_T2_DQS_15_E15") (pintype "bidirectional"))
    )
    (net (code "43") (name "/KEY5") (class "Default")
      (node (ref "U11F") (pin "H15") (pinfunction "IO_L18P_T2_15_H15") (pintype "bidirectional"))
    )
    (net (code "44") (name "/KEY6") (class "Default")
      (node (ref "U11F") (pin "G15") (pinfunction "IO_L18N_T2_15_G15") (pintype "bidirectional"))
    )
    (net (code "45") (name "/KEY7") (class "Default")
      (node (ref "U11F") (pin "H14") (pinfunction "IO_L20N_T3_15_H14") (pintype "bidirectional"))
    )
    (net (code "46") (name "/KEY8") (class "Default")
      (node (ref "U11F") (pin "H16") (pinfunction "IO_L22P_T3_15_H16") (pintype "bidirectional"))
    )
    (net (code "47") (name "/KEY9") (class "Default")
      (node (ref "U11F") (pin "H17") (pinfunction "IO_L22N_T3_15_H17") (pintype "bidirectional"))
    )
    (net (code "48") (name "/KEY10") (class "Default")
      (node (ref "U11F") (pin "E18") (pinfunction "IO_L16N_T2_15_E18") (pintype "bidirectional"))
    )
    (net (code "49") (name "/KEY11") (class "Default")
      (node (ref "U11F") (pin "F18") (pinfunction "IO_L16P_T2_15_F18") (pintype "bidirectional"))
    )
    (net (code "50") (name "/KEY12") (class "Default")
      (node (ref "U11F") (pin "G18") (pinfunction "IO_L21N_T3_DQS_15_G18") (pintype "bidirectional"))
    )
    (net (code "51") (name "/KEY13") (class "Default")
      (node (ref "U11F") (pin "E13") (pinfunction "IO_L17N_T2_15_E13") (pintype "bidirectional"))
    )
    (net (code "52") (name "/KEY14") (class "Default")
      (node (ref "U11F") (pin "H18") (pinfunction "IO_L21P_T3_DQS_15_H18") (pintype "bidirectional"))
    )
    (net (code "53") (name "/KEY15") (class "Default")
      (node (ref "U11F") (pin "F13") (pinfunction "IO_L17P_T2_15_F13") (pintype "bidirectional"))
    )
    (net (code "54") (name "/KEY16") (class "Default")
      (node (ref "U11F") (pin "H13") (pinfunction "IO_L20P_T3_15_H13") (pintype "bidirectional"))
    )
    (net (code "55") (name "/KEY17") (class "Default")
      (node (ref "U11F") (pin "J13") (pinfunction "IO_L24P_T3_RS1_15_J13") (pintype "bidirectional"))
    )
    (net (code "56") (name "/KEY18") (class "Default")
      (node (ref "U11F") (pin "K13") (pinfunction "IO_25_15_K13") (pintype "bidirectional"))
    )
    (net (code "57") (name "/LCD_SCLK") (class "Default")
      (node (ref "U11F") (pin "A17") (pinfunction "IO_L7N_T1_AD10N_15_A17") (pintype "bidirectional"))
    )
    (net (code "58") (name "/LCD_SCS") (class "Default")
      (node (ref "U11F") (pin "C18") (pinfunction "IO_L11N_T1_SRCC_AD12N_15_C18") (pintype "bidirectional"))
    )
    (net (code "59") (name "/LCD_SI") (class "Default")
      (node (ref "U11F") (pin "D17") (pinfunction "IO_L9N_T1_DQS_AD11N_15_D17") (pintype "bidirectional"))
    )
    (net (code "60") (name "/NOISE0") (class "Default")
      (node (ref "U11F") (pin "B13") (pinfunction "IO_L1P_T0_AD0P_15_B13") (pintype "bidirectional"))
    )
    (net (code "61") (name "/NOISE1") (class "Default")
      (node (ref "U11F") (pin "B14") (pinfunction "IO_L2P_T0_AD8P_15_B14") (pintype "bidirectional"))
    )
    (net (code "62") (name "/NOISEBIAS_ON") (class "Default")
      (node (ref "U11F") (pin "A13") (pinfunction "IO_L1N_T0_AD0N_15_A13") (pintype "bidirectional"))
    )
    (net (code "63") (name "/NOISE_ON0") (class "Default")
      (node (ref "U11F") (pin "P14") (pinfunction "IO_L11P_T1_SRCC_14_P14") (pintype "bidirectional"))
    )
    (net (code "64") (name "/NOISE_ON1") (class "Default")
      (node (ref "U11F") (pin "R13") (pinfunction "IO_L19N_T3_D25_VREF_14_R13") (pintype "bidirectional"))
    )
    (net (code "65") (name "/PROG_B") (class "Default")
      (node (ref "P12F") (pin "21") (pinfunction "21_21") (pintype "passive"))
      (node (ref "R24F") (pin "1") (pinfunction "1_1") (pintype "passive"))
      (node (ref "U11F") (pin "R8") (pinfunction "PROGRAM_B_0_R8") (pintype "input"))
      (node (ref "U14F") (pin "1") (pinfunction "VOUT_1") (pintype "output"))
    )
    (net (code "66") (name "/PWR_S0") (class "Default")
      (node (ref "R27F") (pin "1") (pinfunction "1_1") (pintype "passive"))
      (node (ref "U11F") (pin "U6") (pinfunction "IO_L24N_T3_34_U6") (pintype "bidirectional"))
      (node (ref "U16F") (pin "C2") (pinfunction "C_C2") (pintype "input"))
      (node (ref "U17F") (pin "C2") (pinfunction "C_C2") (pintype "input"))
    )
    (net (code "67") (name "/PWR_S1") (class "Default")
      (node (ref "U11F") (pin "L13") (pinfunction "IO_0_14_L13") (pintype "bidirectional"))
    )
    (net (code "68") (name "/RES_CT") (class "Default")
      (node (ref "C34F") (pin "1") (pinfunction "1_1") (pintype "passive"))
      (node (ref "U14F") (pin "5") (pinfunction "CT_5") (pintype "passive"))
    )
    (net (code "69") (name "/RTC_3.3V") (class "Default")
      (node (ref "C64F") (pin "1") (pinfunction "1_1") (pintype "passive"))
      (node (ref "C65F") (pin "1") (pinfunction "1_1") (pintype "passive"))
      (node (ref "R32F") (pin "1") (pinfunction "1_1") (pintype "passive"))
      (node (ref "U18F") (pin "1") (pinfunction "VDD_1") (pintype "power_in"))
    )
    (net (code "70") (name "/RTC_INT1") (class "Default")
      (node (ref "R31F") (pin "2") (pinfunction "2_2") (pintype "passive"))
      (node (ref "U11F") (pin "N5") (pinfunction "IO_L10P_T1_34_N5") (pintype "bidirectional"))
      (node (ref "U18F") (pin "2") (pinfunction "~{INT_1}_2") (pintype "output"))
    )
    (net (code "71") (name "/RTC_WAKE_N") (class "Default")
      (node (ref "R29F") (pin "1") (pinfunction "1_1") (pintype "passive"))
      (node (ref "U18F") (pin "6") (pinfunction "~{INT_2}_6") (pintype "output"))
    )
    (net (code "72") (name "/SPINOR_CSN") (class "Default")
      (node (ref "U11F") (pin "M13") (pinfunction "IO_L6P_T0_FCS_B_14_M13") (pintype "bidirectional"))
    )
    (net (code "73") (name "/SPINOR_DQS") (class "Default")
      (node (ref "U11F") (pin "R14") (pinfunction "IO_L13P_T2_MRCC_14_R14") (pintype "bidirectional"))
    )
    (net (code "74") (name "/SPINOR_ECSN") (class "Default")
      (node (ref "R30F") (pin "2") (pinfunction "2_2") (pintype "passive"))
      (node (ref "U11F") (pin "L16") (pinfunction "IO_L3N_T0_DQS_EMCCLK_14_L16") (pintype "bidirectional"))
    )
    (net (code "75") (name "/SPINOR_IO2") (class "Default")
      (node (ref "U11F") (pin "L14") (pinfunction "IO_L2P_T0_D02_14_L14") (pintype "bidirectional"))
    )
    (net (code "76") (name "/SPINOR_IO3") (class "Default")
      (node (ref "U11F") (pin "M15") (pinfunction "IO_L2N_T0_D03_14_M15") (pintype "bidirectional"))
    )
    (net (code "77") (name "/SPINOR_IO4") (class "Default")
      (node (ref "U11F") (pin "L17") (pinfunction "IO_L4P_T0_D04_14_L17") (pintype "bidirectional"))
    )
    (net (code "78") (name "/SPINOR_IO5") (class "Default")
      (node (ref "U11F") (pin "L18") (pinfunction "IO_L4N_T0_D05_14_L18") (pintype "bidirectional"))
    )
    (net (code "79") (name "/SPINOR_IO6") (class "Default")
      (node (ref "U11F") (pin "M14") (pinfunction "IO_L5P_T0_D06_14_M14") (pintype "bidirectional"))
    )
    (net (code "80") (name "/SPINOR_IO7") (class "Default")
      (node (ref "U11F") (pin "N14") (pinfunction "IO_L5N_T0_D07_14_N14") (pintype "bidirectional"))
    )
    (net (code "81") (name "/SPINOR_MISO") (class "Default")
      (node (ref "U11F") (pin "K18") (pinfunction "IO_L1N_T0_D01_DIN_14_K18") (pintype "bidirectional"))
    )
    (net (code "82") (name "/SPINOR_MOSI") (class "Default")
      (node (ref "U11F") (pin "K17") (pinfunction "IO_L1P_T0_D00_MOSI_14_K17") (pintype "bidirectional"))
    )
    (net (code "83") (name "/SPINOR_SCK") (class "Default")
      (node (ref "U11F") (pin "C8") (pinfunction "CCLK_0_C8") (pintype "input"))
    )
    (net (code "84") (name "/SPK+") (class "Default")
      (node (ref "P11F") (pin "23") (pinfunction "23_23") (pintype "passive"))
      (node (ref "P11F") (pin "24") (pinfunction "24_24") (pintype "passive"))
    )
    (net (code "85") (name "/SPK-") (class "Default")
      (node (ref "P11F") (pin "25") (pinfunction "25_25") (pintype "passive"))
      (node (ref "P11F") (pin "26") (pinfunction "26_26") (pintype "passive"))
    )
    (net (code "86") (name "/SRAM_A0") (class "Default")
      (node (ref "U11F") (pin "V12") (pinfunction "IO_L24N_T3_D16_14_V12") (pintype "bidirectional"))
    )
    (net (code "87") (name "/SRAM_A1") (class "Default")
      (node (ref "U11F") (pin "M5") (pinfunction "IO_L6N_T0_VREF_34_M5") (pintype "bidirectional"))
    )
    (net (code "88") (name "/SRAM_A2") (class "Default")
      (node (ref "U11F") (pin "P5") (pinfunction "IO_L19N_T3_VREF_34_P5") (pintype "bidirectional"))
    )
    (net (code "89") (name "/SRAM_A3") (class "Default")
      (node (ref "U11F") (pin "N4") (pinfunction "IO_L10N_T1_34_N4") (pintype "bidirectional"))
    )
    (net (code "90") (name "/SRAM_A4") (class "Default")
      (node (ref "U11F") (pin "V14") (pinfunction "IO_L20P_T3_D24_14_V14") (pintype "bidirectional"))
    )
    (net (code "91") (name "/SRAM_A5") (class "Default")
      (node (ref "U11F") (pin "M3") (pinfunction "IO_L7P_T1_34_M3") (pintype "bidirectional"))
    )
    (net (code "92") (name "/SRAM_A6") (class "Default")
      (node (ref "U11F") (pin "R17") (pinfunction "IO_L14N_T2_SRCC_14_R17") (pintype "bidirectional"))
    )
    (net (code "93") (name "/SRAM_A7") (class "Default")
      (node (ref "U11F") (pin "U15") (pinfunction "IO_L18P_T2_D28_14_U15") (pintype "bidirectional"))
    )
    (net (code "94") (name "/SRAM_A8") (class "Default")
      (node (ref "U11F") (pin "M4") (pinfunction "IO_L5N_T0_34_M4") (pintype "bidirectional"))
    )
    (net (code "95") (name "/SRAM_A9") (class "Default")
      (node (ref "U11F") (pin "L6") (pinfunction "IO_L4N_T0_34_L6") (pintype "bidirectional"))
    )
    (net (code "96") (name "/SRAM_A10") (class "Default")
      (node (ref "U11F") (pin "K3") (pinfunction "IO_L2P_T0_34_K3") (pintype "bidirectional"))
    )
    (net (code "97") (name "/SRAM_A11") (class "Default")
      (node (ref "U11F") (pin "R18") (pinfunction "IO_L10P_T1_D14_14_R18") (pintype "bidirectional"))
    )
    (net (code "98") (name "/SRAM_A12") (class "Default")
      (node (ref "U11F") (pin "U16") (pinfunction "IO_L16P_T2_CSI_B_14_U16") (pintype "bidirectional"))
    )
    (net (code "99") (name "/SRAM_A13") (class "Default")
      (node (ref "U11F") (pin "K1") (pinfunction "IO_L3P_T0_DQS_34_K1") (pintype "bidirectional"))
    )
    (net (code "100") (name "/SRAM_A14") (class "Default")
      (node (ref "U11F") (pin "R5") (pinfunction "IO_L21P_T3_DQS_34_R5") (pintype "bidirectional"))
    )
    (net (code "101") (name "/SRAM_A15") (class "Default")
      (node (ref "U11F") (pin "T2") (pinfunction "IO_L13N_T2_MRCC_34_T2") (pintype "bidirectional"))
    )
    (net (code "102") (name "/SRAM_A16") (class "Default")
      (node (ref "U11F") (pin "U1") (pinfunction "IO_L14N_T2_SRCC_34_U1") (pintype "bidirectional"))
    )
    (net (code "103") (name "/SRAM_A17") (class "Default")
      (node (ref "U11F") (pin "N1") (pinfunction "IO_L8N_T1_34_N1") (pintype "bidirectional"))
    )
    (net (code "104") (name "/SRAM_A18") (class "Default")
      (node (ref "U11F") (pin "L5") (pinfunction "IO_L5P_T0_34_L5") (pintype "bidirectional"))
    )
    (net (code "105") (name "/SRAM_A19") (class "Default")
      (node (ref "U11F") (pin "K2") (pinfunction "IO_L2N_T0_34_K2") (pintype "bidirectional"))
    )
    (net (code "106") (name "/SRAM_A20") (class "Default")
      (node (ref "U11F") (pin "M18") (pinfunction "IO_L8P_T1_D11_14_M18") (pintype "bidirectional"))
    )
    (net (code "107") (name "/SRAM_A21") (class "Default")
      (node (ref "U11F") (pin "T6") (pinfunction "IO_L22P_T3_34_T6") (pintype "bidirectional"))
    )
    (net (code "108") (name "/SRAM_CE_N") (class "Default")
      (node (ref "U11F") (pin "V5") (pinfunction "IO_L17P_T2_34_V5") (pintype "bidirectional"))
      (node (ref "U16F") (pin "A1") (pinfunction "A_A1") (pintype "passive"))
    )
    (net (code "109") (name "/SRAM_CE_N_1.8") (class "Default")
      (node (ref "U16F") (pin "B1") (pinfunction "B_B1") (pintype "passive"))
    )
    (net (code "110") (name "/SRAM_D0") (class "Default")
      (node (ref "U11F") (pin "M2") (pinfunction "IO_L7N_T1_34_M2") (pintype "bidirectional"))
    )
    (net (code "111") (name "/SRAM_D1") (class "Default")
      (node (ref "U11F") (pin "R4") (pinfunction "IO_L18P_T2_34_R4") (pintype "bidirectional"))
    )
    (net (code "112") (name "/SRAM_D2") (class "Default")
      (node (ref "U11F") (pin "P2") (pinfunction "IO_L11P_T1_SRCC_34_P2") (pintype "bidirectional"))
    )
    (net (code "113") (name "/SRAM_D3") (class "Default")
      (node (ref "U11F") (pin "L4") (pinfunction "IO_L1N_T0_34_L4") (pintype "bidirectional"))
    )
    (net (code "114") (name "/SRAM_D4") (class "Default")
      (node (ref "U11F") (pin "L1") (pinfunction "IO_L3N_T0_DQS_34_L1") (pintype "bidirectional"))
    )
    (net (code "115") (name "/SRAM_D5") (class "Default")
      (node (ref "U11F") (pin "M1") (pinfunction "IO_L8P_T1_34_M1") (pintype "bidirectional"))
    )
    (net (code "116") (name "/SRAM_D6") (class "Default")
      (node (ref "U11F") (pin "R1") (pinfunction "IO_L12N_T1_MRCC_34_R1") (pintype "bidirectional"))
    )
    (net (code "117") (name "/SRAM_D7") (class "Default")
      (node (ref "U11F") (pin "P1") (pinfunction "IO_L11N_T1_SRCC_34_P1") (pintype "bidirectional"))
    )
    (net (code "118") (name "/SRAM_D8") (class "Default")
      (node (ref "U11F") (pin "U3") (pinfunction "IO_L15P_T2_DQS_34_U3") (pintype "bidirectional"))
    )
    (net (code "119") (name "/SRAM_D9") (class "Default")
      (node (ref "U11F") (pin "V2") (pinfunction "IO_L16N_T2_34_V2") (pintype "bidirectional"))
    )
    (net (code "120") (name "/SRAM_D10") (class "Default")
      (node (ref "U11F") (pin "V4") (pinfunction "IO_L17N_T2_34_V4") (pintype "bidirectional"))
    )
    (net (code "121") (name "/SRAM_D11") (class "Default")
      (node (ref "U11F") (pin "U2") (pinfunction "IO_L15N_T2_DQS_34_U2") (pintype "bidirectional"))
    )
    (net (code "122") (name "/SRAM_D12") (class "Default")
      (node (ref "U11F") (pin "N2") (pinfunction "IO_L9N_T1_DQS_34_N2") (pintype "bidirectional"))
    )
    (net (code "123") (name "/SRAM_D13") (class "Default")
      (node (ref "U11F") (pin "T1") (pinfunction "IO_L14P_T2_SRCC_34_T1") (pintype "bidirectional"))
    )
    (net (code "124") (name "/SRAM_D14") (class "Default")
      (node (ref "U11F") (pin "K6") (pinfunction "IO_L4P_T0_34_K6") (pintype "bidirectional"))
    )
    (net (code "125") (name "/SRAM_D15") (class "Default")
      (node (ref "U11F") (pin "J6") (pinfunction "IO_0_34_J6") (pintype "bidirectional"))
    )
    (net (code "126") (name "/SRAM_D16") (class "Default")
      (node (ref "U11F") (pin "V16") (pinfunction "IO_L18N_T2_D27_14_V16") (pintype "bidirectional"))
    )
    (net (code "127") (name "/SRAM_D17") (class "Default")
      (node (ref "U11F") (pin "V15") (pinfunction "IO_L20N_T3_D23_14_V15") (pintype "bidirectional"))
    )
    (net (code "128") (name "/SRAM_D18") (class "Default")
      (node (ref "U11F") (pin "U17") (pinfunction "IO_L15P_T2_DQS_RDWR_B_14_U17") (pintype "bidirectional"))
    )
    (net (code "129") (name "/SRAM_D19") (class "Default")
      (node (ref "U11F") (pin "U18") (pinfunction "IO_L15N_T2_DQS_DOUT_CSO_B_14_U18") (pintype "bidirectional"))
    )
    (net (code "130") (name "/SRAM_D20") (class "Default")
      (node (ref "U11F") (pin "P17") (pinfunction "IO_L9P_T1_DQS_14_P17") (pintype "bidirectional"))
    )
    (net (code "131") (name "/SRAM_D21") (class "Default")
      (node (ref "U11F") (pin "T18") (pinfunction "IO_L10N_T1_D15_14_T18") (pintype "bidirectional"))
    )
    (net (code "132") (name "/SRAM_D22") (class "Default")
      (node (ref "U11F") (pin "P18") (pinfunction "IO_L9N_T1_DQS_D13_14_P18") (pintype "bidirectional"))
    )
    (net (code "133") (name "/SRAM_D23") (class "Default")
      (node (ref "U11F") (pin "M17") (pinfunction "IO_L7N_T1_D10_14_M17") (pintype "bidirectional"))
    )
    (net (code "134") (name "/SRAM_D24") (class "Default")
      (node (ref "U11F") (pin "N3") (pinfunction "IO_L9P_T1_DQS_34_N3") (pintype "bidirectional"))
    )
    (net (code "135") (name "/SRAM_D25") (class "Default")
      (node (ref "U11F") (pin "T4") (pinfunction "IO_L21N_T3_DQS_34_T4") (pintype "bidirectional"))
    )
    (net (code "136") (name "/SRAM_D26") (class "Default")
      (node (ref "U11F") (pin "V13") (pinfunction "IO_L21N_T3_DQS_D22_14_V13") (pintype "bidirectional"))
    )
    (net (code "137") (name "/SRAM_D27") (class "Default")
      (node (ref "U11F") (pin "P15") (pinfunction "IO_L11N_T1_SRCC_14_P15") (pintype "bidirectional"))
    )
    (net (code "138") (name "/SRAM_D28") (class "Default")
      (node (ref "U11F") (pin "T14") (pinfunction "IO_L13N_T2_MRCC_14_T14") (pintype "bidirectional"))
    )
    (net (code "139") (name "/SRAM_D29") (class "Default")
      (node (ref "U11F") (pin "R15") (pinfunction "IO_L17P_T2_D30_14_R15") (pintype "bidirectional"))
    )
    (net (code "140") (name "/SRAM_D30") (class "Default")
      (node (ref "U11F") (pin "T3") (pinfunction "IO_L18N_T2_34_T3") (pintype "bidirectional"))
    )
    (net (code "141") (name "/SRAM_D31") (class "Default")
      (node (ref "U11F") (pin "R7") (pinfunction "IO_L23P_T3_34_R7") (pintype "bidirectional"))
    )
    (net (code "142") (name "/SRAM_DM0") (class "Default")
      (node (ref "U11F") (pin "V3") (pinfunction "IO_L16P_T2_34_V3") (pintype "bidirectional"))
    )
    (net (code "143") (name "/SRAM_DM1") (class "Default")
      (node (ref "U11F") (pin "R2") (pinfunction "IO_L12P_T1_MRCC_34_R2") (pintype "bidirectional"))
    )
    (net (code "144") (name "/SRAM_DM2") (class "Default")
      (node (ref "U11F") (pin "T5") (pinfunction "IO_L22N_T3_34_T5") (pintype "bidirectional"))
    )
    (net (code "145") (name "/SRAM_DM3") (class "Default")
      (node (ref "U11F") (pin "T13") (pinfunction "IO_L22N_T3_D20_14_T13") (pintype "bidirectional"))
    )
    (net (code "146") (name "/SRAM_OE_N") (class "Default")
      (node (ref "U11F") (pin "U12") (pinfunction "IO_L21P_T3_DQS_14_U12") (pintype "bidirectional"))
    )
    (net (code "147") (name "/SRAM_WE_N") (class "Default")
      (node (ref "U11F") (pin "K4") (pinfunction "IO_L1P_T0_34_K4") (pintype "bidirectional"))
    )
    (net (code "148") (name "/SRAM_ZZ_N") (class "Default")
      (node (ref "U11F") (pin "V17") (pinfunction "IO_L16N_T2_D31_14_V17") (pintype "bidirectional"))
      (node (ref "U17F") (pin "A1") (pinfunction "A_A1") (pintype "passive"))
    )
    (net (code "149") (name "/SRAM_ZZ_N_1.8") (class "Default")
      (node (ref "U17F") (pin "B1") (pinfunction "B_B1") (pintype "passive"))
    )
    (net (code "150") (name "/SW_0.95V") (class "Default")
      (node (ref "L12F") (pin "1") (pinfunction "1_1") (pintype "passive"))
      (node (ref "U12F") (pin "B2") (pinfunction "SW_B2") (pintype "output"))
    )
    (net (code "151") (name "/SW_1.8V_F") (class "Default")
      (node (ref "L13F") (pin "1") (pinfunction "1_1") (pintype "passive"))
      (node (ref "U13F") (pin "B2") (pinfunction "SW_B2") (pintype "output"))
    )
    (net (code "152") (name "/TF_CLK") (class "Default")
      (node (ref "J13F") (pin "5") (pinfunction "CLK_5") (pintype "input"))
      (node (ref "U11F") (pin "G16") (pinfunction "IO_L14P_T2_SRCC_15_G16") (pintype "bidirectional"))
    )
    (net (code "153") (name "/TF_CMD") (class "Default")
      (node (ref "J13F") (pin "3") (pinfunction "CMD_3") (pintype "bidirectional"))
      (node (ref "R33F") (pin "2") (pinfunction "2_2") (pintype "passive"))
      (node (ref "U11F") (pin "J16") (pinfunction "IO_L19N_T3_VREF_15_J16") (pintype "bidirectional"))
    )
    (net (code "154") (name "/TF_D0") (class "Default")
      (node (ref "J13F") (pin "7") (pinfunction "DAT0_7") (pintype "bidirectional"))
      (node (ref "U11F") (pin "J15") (pinfunction "IO_L23N_T3_15_J15") (pintype "bidirectional"))
    )
    (net (code "155") (name "/TF_D1") (class "Default")
      (node (ref "J13F") (pin "8") (pinfunction "DAT1_8") (pintype "bidirectional"))
      (node (ref "U11F") (pin "J14") (pinfunction "IO_L24N_T3_RS0_15_J14") (pintype "bidirectional"))
    )
    (net (code "156") (name "/TF_D2") (class "Default")
      (node (ref "J13F") (pin "1") (pinfunction "DAT2_1") (pintype "bidirectional"))
      (node (ref "U11F") (pin "K16") (pinfunction "IO_L19P_T3_15_K16") (pintype "bidirectional"))
    )
    (net (code "157") (name "/TF_D3") (class "Default")
      (node (ref "J13F") (pin "2") (pinfunction "CD/DAT3_2") (pintype "bidirectional"))
      (node (ref "U11F") (pin "K14") (pinfunction "IO_L23P_T3_15_K14") (pintype "bidirectional"))
    )
    (net (code "158") (name "/T_OFF") (class "Default")
      (node (ref "Q10F") (pin "1") (pinfunction "G_1") (pintype "passive"))
      (node (ref "Q11F") (pin "3") (pinfunction "D_3") (pintype "passive"))
      (node (ref "Q12F") (pin "3") (pinfunction "D_3") (pintype "passive"))
      (node (ref "Q13F") (pin "3") (pinfunction "D_3") (pintype "passive"))
      (node (ref "R10F") (pin "1") (pinfunction "1_1") (pintype "passive"))
      (node (ref "R29F") (pin "2") (pinfunction "2_2") (pintype "passive"))
    )
    (net (code "159") (name "/UP5K_CSN") (class "Default")
      (node (ref "P12F") (pin "5") (pinfunction "5_5") (pintype "passive"))
    )
    (net (code "160") (name "/UP5K_KEYCOL0") (class "Default")
      (node (ref "P12F") (pin "19") (pinfunction "19_19") (pintype "passive"))
    )
    (net (code "161") (name "/UP5K_KEYCOL1") (class "Default")
      (node (ref "P12F") (pin "20") (pinfunction "20_20") (pintype "passive"))
    )
    (net (code "162") (name "/UP5K_MISO") (class "Default")
      (node (ref "P12F") (pin "7") (pinfunction "7_7") (pintype "passive"))
    )
    (net (code "163") (name "/UP5K_MOSI") (class "Default")
      (node (ref "P12F") (pin "6") (pinfunction "6_6") (pintype "passive"))
    )
    (net (code "164") (name "/UP5K_RGB0") (class "Default")
      (node (ref "P11F") (pin "20") (pinfunction "20_20") (pintype "passive"))
    )
    (net (code "165") (name "/UP5K_RGB1") (class "Default")
      (node (ref "P11F") (pin "21") (pinfunction "21_21") (pintype "passive"))
    )
    (net (code "166") (name "/UP5K_RGB2") (class "Default")
      (node (ref "P11F") (pin "22") (pinfunction "22_22") (pintype "passive"))
    )
    (net (code "167") (name "/UP5K_SCK") (class "Default")
      (node (ref "P12F") (pin "8") (pinfunction "8_8") (pintype "passive"))
    )
    (net (code "168") (name "/USBC_CC1") (class "Default")
      (node (ref "U11F") (pin "C17") (pinfunction "IO_L8P_T1_AD3P_15_C17") (pintype "bidirectional"))
    )
    (net (code "169") (name "/USBC_CC2") (class "Default")
      (node (ref "U11F") (pin "E16") (pinfunction "IO_L10P_T1_AD4P_15_E16") (pintype "bidirectional"))
    )
    (net (code "170") (name "/U_TO_T_ON") (class "Default")
      (node (ref "Q13F") (pin "1") (pinfunction "G_1") (pintype "passive"))
      (node (ref "R28F") (pin "2") (pinfunction "2_2") (pintype "passive"))
    )
    (net (code "171") (name "/VBUS_DIV") (class "Default")
      (node (ref "U11F") (pin "E12") (pinfunction "IO_L5P_T0_AD2P_15_E12") (pintype "bidirectional"))
    )
    (net (code "173") (name "/WIFI_LPCLK") (class "Default")
      (node (ref "U11F") (pin "N15") (pinfunction "IO_L12P_T1_MRCC_14_N15") (pintype "bidirectional"))
    )
    (net (code "174") (name "/XADC_GND") (class "Default")
      (node (ref "C10F") (pin "2") (pinfunction "2_2") (pintype "passive"))
      (node (ref "C11F") (pin "2") (pinfunction "2_2") (pintype "passive"))
      (node (ref "C12F") (pin "2") (pinfunction "2_2") (pintype "passive"))
      (node (ref "C13F") (pin "2") (pinfunction "2_2") (pintype "passive"))
      (node (ref "C69F") (pin "2") (pinfunction "2_2") (pintype "passive"))
      (node (ref "C70F") (pin "2") (pinfunction "2_2") (pintype "passive"))
      (node (ref "L11F") (pin "2") (pinfunction "2_2") (pintype "passive"))
      (node (ref "U10F") (pin "3") (pinfunction "GND_3") (pintype "power_in"))
      (node (ref "U11F") (pin "H9") (pinfunction "GNDADC_0_H9") (pintype "power_in"))
      (node (ref "U11F") (pin "J9") (pinfunction "VREFN_0_J9") (pintype "power_in"))
      (node (ref "U11F") (pin "L10") (pinfunction "DXP_0_L10") (pintype "passive"))
      (node (ref "U11F") (pin "L9") (pinfunction "DXN_0_L9") (pintype "passive"))
    )
    (net (code "175") (name "/XADC_VDD") (class "Default")
      (node (ref "C10F") (pin "1") (pinfunction "1_1") (pintype "passive"))
      (node (ref "C13F") (pin "1") (pinfunction "1_1") (pintype "passive"))
      (node (ref "C69F") (pin "1") (pinfunction "1_1") (pintype "passive"))
      (node (ref "L10F") (pin "2") (pinfunction "2_2") (pintype "passive"))
      (node (ref "U10F") (pin "1") (pinfunction "IN_1") (pintype "power_in"))
      (node (ref "U11F") (pin "H10") (pinfunction "VCCADC_0_H10") (pintype "power_in"))
    )
    (net (code "176") (name "/XADC_VREF") (class "Default")
      (node (ref "C11F") (pin "1") (pinfunction "1_1") (pintype "passive"))
      (node (ref "C12F") (pin "1") (pinfunction "1_1") (pintype "passive"))
      (node (ref "C70F") (pin "1") (pinfunction "1_1") (pintype "passive"))
      (node (ref "U10F") (pin "2") (pinfunction "OUT_2") (pintype "power_in"))
      (node (ref "U11F") (pin "K10") (pinfunction "VREFP_0_K10") (pintype "power_in"))
    )
    (net (code "177") (name "GND") (class "Default")
      (node (ref "C14F") (pin "2") (pinfunction "2_2") (pintype "passive"))
      (node (ref "C15F") (pin "2") (pinfunction "2_2") (pintype "passive"))
      (node (ref "C16F") (pin "2") (pinfunction "2_2") (pintype "passive"))
      (node (ref "C17F") (pin "2") (pinfunction "2_2") (pintype "passive"))
      (node (ref "C18F") (pin "2") (pinfunction "2_2") (pintype "passive"))
      (node (ref "C19F") (pin "2") (pinfunction "2_2") (pintype "passive"))
      (node (ref "C20F") (pin "2") (pinfunction "2_2") (pintype "passive"))
      (node (ref "C21F") (pin "2") (pinfunction "2_2") (pintype "passive"))
      (node (ref "C22F") (pin "1") (pinfunction "1_1") (pintype "passive"))
      (node (ref "C23F") (pin "2") (pinfunction "2_2") (pintype "passive"))
      (node (ref "C24F") (pin "2") (pinfunction "2_2") (pintype "passive"))
      (node (ref "C25F") (pin "2") (pinfunction "2_2") (pintype "passive"))
      (node (ref "C26F") (pin "2") (pinfunction "2_2") (pintype "passive"))
      (node (ref "C27F") (pin "1") (pinfunction "1_1") (pintype "passive"))
      (node (ref "C28F") (pin "2") (pinfunction "2_2") (pintype "passive"))
      (node (ref "C29F") (pin "2") (pinfunction "2_2") (pintype "passive"))
      (node (ref "C30F") (pin "1") (pinfunction "1_1") (pintype "passive"))
      (node (ref "C31F") (pin "2") (pinfunction "2_2") (pintype "passive"))
      (node (ref "C32F") (pin "2") (pinfunction "2_2") (pintype "passive"))
      (node (ref "C33F") (pin "2") (pinfunction "2_2") (pintype "passive"))
      (node (ref "C34F") (pin "2") (pinfunction "2_2") (pintype "passive"))
      (node (ref "C35F") (pin "2") (pinfunction "2_2") (pintype "passive"))
      (node (ref "C36F") (pin "2") (pinfunction "2_2") (pintype "passive"))
      (node (ref "C37F") (pin "1") (pinfunction "1_1") (pintype "passive"))
      (node (ref "C38F") (pin "2") (pinfunction "2_2") (pintype "passive"))
      (node (ref "C39F") (pin "2") (pinfunction "2_2") (pintype "passive"))
      (node (ref "C40F") (pin "1") (pinfunction "1_1") (pintype "passive"))
      (node (ref "C41F") (pin "2") (pinfunction "2_2") (pintype "passive"))
      (node (ref "C42F") (pin "2") (pinfunction "2_2") (pintype "passive"))
      (node (ref "C43F") (pin "2") (pinfunction "2_2") (pintype "passive"))
      (node (ref "C44F") (pin "2") (pinfunction "2_2") (pintype "passive"))
      (node (ref "C45F") (pin "2") (pinfunction "2_2") (pintype "passive"))
      (node (ref "C46F") (pin "2") (pinfunction "2_2") (pintype "passive"))
      (node (ref "C47F") (pin "1") (pinfunction "1_1") (pintype "passive"))
      (node (ref "C48F") (pin "2") (pinfunction "2_2") (pintype "passive"))
      (node (ref "C49F") (pin "2") (pinfunction "2_2") (pintype "passive"))
      (node (ref "C50F") (pin "2") (pinfunction "2_2") (pintype "passive"))
      (node (ref "C51F") (pin "2") (pinfunction "2_2") (pintype "passive"))
      (node (ref "C52F") (pin "1") (pinfunction "1_1") (pintype "passive"))
      (node (ref "C53F") (pin "2") (pinfunction "2_2") (pintype "passive"))
      (node (ref "C54F") (pin "2") (pinfunction "2_2") (pintype "passive"))
      (node (ref "C55F") (pin "1") (pinfunction "1_1") (pintype "passive"))
      (node (ref "C56F") (pin "2") (pinfunction "2_2") (pintype "passive"))
      (node (ref "C57F") (pin "2") (pinfunction "2_2") (pintype "passive"))
      (node (ref "C58F") (pin "2") (pinfunction "2_2") (pintype "passive"))
      (node (ref "C59F") (pin "2") (pinfunction "2_2") (pintype "passive"))
      (node (ref "C60F") (pin "2") (pinfunction "2_2") (pintype "passive"))
      (node (ref "C61F") (pin "2") (pinfunction "2_2") (pintype "passive"))
      (node (ref "C62F") (pin "2") (pinfunction "2_2") (pintype "passive"))
      (node (ref "C63F") (pin "2") (pinfunction "2_2") (pintype "passive"))
      (node (ref "C64F") (pin "2") (pinfunction "2_2") (pintype "passive"))
      (node (ref "C65F") (pin "2") (pinfunction "2_2") (pintype "passive"))
      (node (ref "C66F") (pin "2") (pinfunction "2_2") (pintype "passive"))
      (node (ref "C67F") (pin "2") (pinfunction "2_2") (pintype "passive"))
      (node (ref "C68F") (pin "2") (pinfunction "2_2") (pintype "passive"))
      (node (ref "C71F") (pin "2") (pinfunction "2_2") (pintype "passive"))
      (node (ref "C72F") (pin "2") (pinfunction "2_2") (pintype "passive"))
      (node (ref "C73F") (pin "2") (pinfunction "2_2") (pintype "passive"))
      (node (ref "C74F") (pin "2") (pinfunction "2_2") (pintype "passive"))
      (node (ref "C75F") (pin "2") (pinfunction "2_2") (pintype "passive"))
      (node (ref "C76F") (pin "2") (pinfunction "2_2") (pintype "passive"))
      (node (ref "C77F") (pin "2") (pinfunction "2_2") (pintype "passive"))
      (node (ref "C78F") (pin "2") (pinfunction "2_2") (pintype "passive"))
      (node (ref "C79F") (pin "2") (pinfunction "2_2") (pintype "passive"))
      (node (ref "C80F") (pin "2") (pinfunction "2_2") (pintype "passive"))
      (node (ref "C81F") (pin "2") (pinfunction "2_2") (pintype "passive"))
      (node (ref "C82F") (pin "2") (pinfunction "2_2") (pintype "passive"))
      (node (ref "C83F") (pin "2") (pinfunction "2_2") (pintype "passive"))
      (node (ref "C84F") (pin "2") (pinfunction "2_2") (pintype "passive"))
      (node (ref "C85F") (pin "2") (pinfunction "2_2") (pintype "passive"))
      (node (ref "C86F") (pin "2") (pinfunction "2_2") (pintype "passive"))
      (node (ref "C87F") (pin "2") (pinfunction "2_2") (pintype "passive"))
      (node (ref "C88F") (pin "2") (pinfunction "2_2") (pintype "passive"))
      (node (ref "C89F") (pin "2") (pinfunction "2_2") (pintype "passive"))
      (node (ref "C90F") (pin "2") (pinfunction "2_2") (pintype "passive"))
      (node (ref "C91F") (pin "2") (pinfunction "2_2") (pintype "passive"))
      (node (ref "J13F") (pin "6") (pinfunction "VSS_6") (pintype "power_in"))
      (node (ref "L11F") (pin "1") (pinfunction "1_1") (pintype "passive"))
      (node (ref "P11F") (pin "1") (pinfunction "1_1") (pintype "passive"))
      (node (ref "P11F") (pin "15") (pinfunction "15_15") (pintype "passive"))
      (node (ref "P11F") (pin "2") (pinfunction "2_2") (pintype "passive"))
      (node (ref "P11F") (pin "3") (pinfunction "3_3") (pintype "passive"))
      (node (ref "P11F") (pin "7") (pinfunction "7_7") (pintype "passive"))
      (node (ref "P11F") (pin "8") (pinfunction "8_8") (pintype "passive"))
      (node (ref "P12F") (pin "1") (pinfunction "1_1") (pintype "passive"))
      (node (ref "P12F") (pin "11") (pinfunction "11_11") (pintype "passive"))
      (node (ref "P12F") (pin "16") (pinfunction "16_16") (pintype "passive"))
      (node (ref "P12F") (pin "17") (pinfunction "17_17") (pintype "passive"))
      (node (ref "P12F") (pin "24") (pinfunction "24_24") (pintype "passive"))
      (node (ref "Q11F") (pin "2") (pinfunction "S_2") (pintype "passive"))
      (node (ref "Q12F") (pin "2") (pinfunction "S_2") (pintype "passive"))
      (node (ref "Q13F") (pin "2") (pinfunction "S_2") (pintype "passive"))
      (node (ref "Q14F") (pin "2") (pinfunction "S_2") (pintype "passive"))
      (node (ref "Q15F") (pin "2") (pinfunction "S_2") (pintype "passive"))
      (node (ref "R11F") (pin "2") (pinfunction "2_2") (pintype "passive"))
      (node (ref "R14F") (pin "1") (pinfunction "1_1") (pintype "passive"))
      (node (ref "R17F") (pin "1") (pinfunction "1_1") (pintype "passive"))
      (node (ref "R18F") (pin "1") (pinfunction "1_1") (pintype "passive"))
      (node (ref "R23F") (pin "1") (pinfunction "1_1") (pintype "passive"))
      (node (ref "R27F") (pin "2") (pinfunction "2_2") (pintype "passive"))
      (node (ref "R28F") (pin "1") (pinfunction "1_1") (pintype "passive"))
      (node (ref "U11F") (pin "A1") (pinfunction "GND_A1") (pintype "power_in"))
      (node (ref "U11F") (pin "A12") (pinfunction "GND_A12") (pintype "power_in"))
      (node (ref "U11F") (pin "A18") (pinfunction "GND_A18") (pintype "power_in"))
      (node (ref "U11F") (pin "B8") (pinfunction "VCCBATT_0_B8") (pintype "power_in"))
      (node (ref "U11F") (pin "B9") (pinfunction "GND_B9") (pintype "power_in"))
      (node (ref "U11F") (pin "C16") (pinfunction "GND_C16") (pintype "power_in"))
      (node (ref "U11F") (pin "C6") (pinfunction "GND_C6") (pintype "power_in"))
      (node (ref "U11F") (pin "D13") (pinfunction "GND_D13") (pintype "power_in"))
      (node (ref "U11F") (pin "D3") (pinfunction "GND_D3") (pintype "power_in"))
      (node (ref "U11F") (pin "E10") (pinfunction "GND_E10") (pintype "power_in"))
      (node (ref "U11F") (pin "E8") (pinfunction "GND_E8") (pintype "power_in"))
      (node (ref "U11F") (pin "F11") (pinfunction "GND_F11") (pintype "power_in"))
      (node (ref "U11F") (pin "F17") (pinfunction "GND_F17") (pintype "power_in"))
      (node (ref "U11F") (pin "F7") (pinfunction "GND_F7") (pintype "power_in"))
      (node (ref "U11F") (pin "F9") (pinfunction "GND_F9") (pintype "power_in"))
      (node (ref "U11F") (pin "G10") (pinfunction "GND_G10") (pintype "power_in"))
      (node (ref "U11F") (pin "G12") (pinfunction "GND_G12") (pintype "power_in"))
      (node (ref "U11F") (pin "G14") (pinfunction "GND_G14") (pintype "power_in"))
      (node (ref "U11F") (pin "G4") (pinfunction "GND_G4") (pintype "power_in"))
      (node (ref "U11F") (pin "G8") (pinfunction "GND_G8") (pintype "power_in"))
      (node (ref "U11F") (pin "H1") (pinfunction "GND_H1") (pintype "power_in"))
      (node (ref "U11F") (pin "H11") (pinfunction "GND_H11") (pintype "power_in"))
      (node (ref "U11F") (pin "H7") (pinfunction "GND_H7") (pintype "power_in"))
      (node (ref "U11F") (pin "J12") (pinfunction "GND_J12") (pintype "power_in"))
      (node (ref "U11F") (pin "J18") (pinfunction "GND_J18") (pintype "power_in"))
      (node (ref "U11F") (pin "J8") (pinfunction "GND_J8") (pintype "power_in"))
      (node (ref "U11F") (pin "K11") (pinfunction "GND_K11") (pintype "power_in"))
      (node (ref "U11F") (pin "K15") (pinfunction "GND_K15") (pintype "power_in"))
      (node (ref "U11F") (pin "K5") (pinfunction "GND_K5") (pintype "power_in"))
      (node (ref "U11F") (pin "K7") (pinfunction "GND_K7") (pintype "power_in"))
      (node (ref "U11F") (pin "L12") (pinfunction "GND_L12") (pintype "power_in"))
      (node (ref "U11F") (pin "L2") (pinfunction "GND_L2") (pintype "power_in"))
      (node (ref "U11F") (pin "L8") (pinfunction "GND_L8") (pintype "power_in"))
      (node (ref "U11F") (pin "M11") (pinfunction "GND_M11") (pintype "power_in"))
      (node (ref "U11F") (pin "M7") (pinfunction "GND_M7") (pintype "power_in"))
      (node (ref "U11F") (pin "M9") (pinfunction "GND_M9") (pintype "power_in"))
      (node (ref "U11F") (pin "N10") (pinfunction "GND_N10") (pintype "power_in"))
      (node (ref "U11F") (pin "N12") (pinfunction "GND_N12") (pintype "power_in"))
      (node (ref "U11F") (pin "N16") (pinfunction "GND_N16") (pintype "power_in"))
      (node (ref "U11F") (pin "N6") (pinfunction "GND_N6") (pintype "power_in"))
      (node (ref "U11F") (pin "N8") (pinfunction "GND_N8") (pintype "power_in"))
      (node (ref "U11F") (pin "P11") (pinfunction "GND_P11") (pintype "power_in"))
      (node (ref "U11F") (pin "P3") (pinfunction "GND_P3") (pintype "power_in"))
      (node (ref "U11F") (pin "P9") (pinfunction "GND_P9") (pintype "power_in"))
      (node (ref "U11F") (pin "R10") (pinfunction "GND_R10") (pintype "power_in"))
      (node (ref "U11F") (pin "T17") (pinfunction "GND_T17") (pintype "power_in"))
      (node (ref "U11F") (pin "T7") (pinfunction "GND_T7") (pintype "power_in"))
      (node (ref "U11F") (pin "U14") (pinfunction "GND_U14") (pintype "power_in"))
      (node (ref "U11F") (pin "U4") (pinfunction "GND_U4") (pintype "power_in"))
      (node (ref "U11F") (pin "V1") (pinfunction "GND_V1") (pintype "power_in"))
      (node (ref "U11F") (pin "V11") (pinfunction "GND_V11") (pintype "power_in"))
      (node (ref "U11F") (pin "V18") (pinfunction "GND_V18") (pintype "power_in"))
      (node (ref "U11F") (pin "V9") (pinfunction "CFGBVS_0_V9") (pintype "input"))
      (node (ref "U12F") (pin "A1") (pinfunction "GND_A1") (pintype "power_in"))
      (node (ref "U13F") (pin "A1") (pinfunction "GND_A1") (pintype "power_in"))
      (node (ref "U13F") (pin "C1") (pinfunction "VSEL/MODE_C1") (pintype "input"))
      (node (ref "U14F") (pin "3") (pinfunction "GND_3") (pintype "power_in"))
      (node (ref "U15F") (pin "1") (pinfunction "ST_1") (pintype "input"))
      (node (ref "U15F") (pin "4") (pinfunction "GND_4") (pintype "power_in"))
      (node (ref "U16F") (pin "C1") (pinfunction "GND_C1") (pintype "power_in"))
      (node (ref "U17F") (pin "C1") (pinfunction "GND_C1") (pintype "power_in"))
      (node (ref "U18F") (pin "7") (pinfunction "VSS_7") (pintype "power_in"))
    )
    (net (code "178") (name "Net-(Q14F-D)") (class "Default")
      (node (ref "Q14F") (pin "3") (pinfunction "D_3") (pintype "passive"))
      (node (ref "R20F") (pin "1") (pinfunction "1_1") (pintype "passive"))
    )
    (net (code "179") (name "Net-(Q15F-D)") (class "Default")
      (node (ref "Q15F") (pin "3") (pinfunction "D_3") (pintype "passive"))
      (node (ref "R21F") (pin "1") (pinfunction "1_1") (pintype "passive"))
    )
    (net (code "180") (name "Net-(U11FA-DONE_0)") (class "Default")
      (node (ref "R13F") (pin "1") (pinfunction "1_1") (pintype "passive"))
      (node (ref "U11F") (pin "V8") (pinfunction "DONE_0_V8") (pintype "open_collector"))
    )
    (net (code "181") (name "Net-(U11FA-M0_0)") (class "Default")
      (node (ref "R19F") (pin "2") (pinfunction "2_2") (pintype "passive"))
      (node (ref "U11F") (pin "T10") (pinfunction "M0_0_T10") (pintype "input"))
    )
    (net (code "182") (name "Net-(U11FA-M1_0)") (class "Default")
      (node (ref "R18F") (pin "2") (pinfunction "2_2") (pintype "passive"))
      (node (ref "U11F") (pin "U10") (pinfunction "M1_0_U10") (pintype "input"))
    )
    (net (code "183") (name "Net-(U11FA-M2_0)") (class "Default")
      (node (ref "P10F") (pin "1") (pinfunction "1_1") (pintype "passive"))
      (node (ref "R17F") (pin "2") (pinfunction "2_2") (pintype "passive"))
      (node (ref "U11F") (pin "U9") (pinfunction "M2_0_U9") (pintype "input"))
    )
    (net (code "184") (name "Net-(U11FB-IO_L3P_T0_DQS_PUDC_B_14)") (class "Default")
      (node (ref "R22F") (pin "1") (pinfunction "1_1") (pintype "passive"))
      (node (ref "U11F") (pin "L15") (pinfunction "IO_L3P_T0_DQS_PUDC_B_14_L15") (pintype "bidirectional"))
    )
    (net (code "185") (name "Net-(U12F-EN)") (class "Default")
      (node (ref "R12F") (pin "1") (pinfunction "1_1") (pintype "passive"))
      (node (ref "U12F") (pin "C2") (pinfunction "EN_C2") (pintype "input"))
    )
    (net (code "186") (name "Net-(U12F-VSEL{slash}MODE)") (class "Default")
      (node (ref "R11F") (pin "1") (pinfunction "1_1") (pintype "passive"))
      (node (ref "U12F") (pin "C1") (pinfunction "VSEL/MODE_C1") (pintype "input"))
    )
    (net (code "187") (name "Net-(U13F-EN)") (class "Default")
      (node (ref "R16F") (pin "2") (pinfunction "2_2") (pintype "passive"))
      (node (ref "U13F") (pin "C2") (pinfunction "EN_C2") (pintype "input"))
    )
    (net (code "188") (name "P0.95V_T") (class "Default")
      (node (ref "C16F") (pin "1") (pinfunction "1_1") (pintype "passive"))
      (node (ref "C19F") (pin "1") (pinfunction "1_1") (pintype "passive"))
      (node (ref "C20F") (pin "1") (pinfunction "1_1") (pintype "passive"))
      (node (ref "C21F") (pin "1") (pinfunction "1_1") (pintype "passive"))
      (node (ref "C22F") (pin "2") (pinfunction "2_2") (pintype "passive"))
      (node (ref "C23F") (pin "1") (pinfunction "1_1") (pintype "passive"))
      (node (ref "C24F") (pin "1") (pinfunction "1_1") (pintype "passive"))
      (node (ref "C25F") (pin "1") (pinfunction "1_1") (pintype "passive"))
      (node (ref "C26F") (pin "1") (pinfunction "1_1") (pintype "passive"))
      (node (ref "C27F") (pin "2") (pinfunction "2_2") (pintype "passive"))
      (node (ref "C28F") (pin "1") (pinfunction "1_1") (pintype "passive"))
      (node (ref "C60F") (pin "1") (pinfunction "1_1") (pintype "passive"))
      (node (ref "C61F") (pin "1") (pinfunction "1_1") (pintype "passive"))
      (node (ref "C71F") (pin "1") (pinfunction "1_1") (pintype "passive"))
      (node (ref "C72F") (pin "1") (pinfunction "1_1") (pintype "passive"))
      (node (ref "C73F") (pin "1") (pinfunction "1_1") (pintype "passive"))
      (node (ref "C74F") (pin "1") (pinfunction "1_1") (pintype "passive"))
      (node (ref "C75F") (pin "1") (pinfunction "1_1") (pintype "passive"))
      (node (ref "C76F") (pin "1") (pinfunction "1_1") (pintype "passive"))
      (node (ref "C89F") (pin "1") (pinfunction "1_1") (pintype "passive"))
      (node (ref "L12F") (pin "2") (pinfunction "2_2") (pintype "passive"))
      (node (ref "R16F") (pin "1") (pinfunction "1_1") (pintype "passive"))
      (node (ref "R20F") (pin "2") (pinfunction "2_2") (pintype "passive"))
      (node (ref "U11F") (pin "E11") (pinfunction "VCCINT_E11") (pintype "power_in"))
      (node (ref "U11F") (pin "E7") (pinfunction "VCCINT_E7") (pintype "power_in"))
      (node (ref "U11F") (pin "E9") (pinfunction "VCCINT_E9") (pintype "power_in"))
      (node (ref "U11F") (pin "F10") (pinfunction "VCCINT_F10") (pintype "power_in"))
      (node (ref "U11F") (pin "F8") (pinfunction "VCCINT_F8") (pintype "power_in"))
      (node (ref "U11F") (pin "G11") (pinfunction "VCCINT_G11") (pintype "power_in"))
      (node (ref "U11F") (pin "G7") (pinfunction "VCCINT_G7") (pintype "power_in"))
      (node (ref "U11F") (pin "G9") (pinfunction "VCCINT_G9") (pintype "power_in"))
      (node (ref "U11F") (pin "H8") (pinfunction "VCCINT_H8") (pintype "power_in"))
      (node (ref "U11F") (pin "J11") (pinfunction "VCCINT_J11") (pintype "power_in"))
      (node (ref "U11F") (pin "J7") (pinfunction "VCCINT_J7") (pintype "power_in"))
      (node (ref "U11F") (pin "K8") (pinfunction "VCCINT_K8") (pintype "power_in"))
      (node (ref "U11F") (pin "L11") (pinfunction "VCCINT_L11") (pintype "power_in"))
      (node (ref "U11F") (pin "L7") (pinfunction "VCCBRAM_L7") (pintype "power_in"))
      (node (ref "U11F") (pin "M10") (pinfunction "VCCINT_M10") (pintype "power_in"))
      (node (ref "U11F") (pin "M8") (pinfunction "VCCINT_M8") (pintype "power_in"))
      (node (ref "U11F") (pin "N11") (pinfunction "VCCINT_N11") (pintype "power_in"))
      (node (ref "U11F") (pin "N7") (pinfunction "VCCBRAM_N7") (pintype "power_in"))
      (node (ref "U11F") (pin "N9") (pinfunction "VCCINT_N9") (pintype "power_in"))
      (node (ref "U11F") (pin "P10") (pinfunction "VCCINT_P10") (pintype "power_in"))
      (node (ref "U11F") (pin "P8") (pinfunction "VCCINT_P8") (pintype "power_in"))
      (node (ref "U12F") (pin "A2") (pinfunction "VOS_A2") (pintype "input"))
    )
    (net (code "189") (name "P1.8V") (class "Default")
      (node (ref "C37F") (pin "2") (pinfunction "2_2") (pintype "passive"))
      (node (ref "P11F") (pin "16") (pinfunction "16_16") (pintype "passive"))
      (node (ref "P12F") (pin "9") (pinfunction "9_9") (pintype "passive"))
      (node (ref "U16F") (pin "A2") (pinfunction "VCC_A2") (pintype "power_in"))
      (node (ref "U17F") (pin "A2") (pinfunction "VCC_A2") (pintype "power_in"))
    )
    (net (code "190") (name "P1.8V_T") (class "Default")
      (node (ref "C18F") (pin "1") (pinfunction "1_1") (pintype "passive"))
      (node (ref "C29F") (pin "1") (pinfunction "1_1") (pintype "passive"))
      (node (ref "C30F") (pin "2") (pinfunction "2_2") (pintype "passive"))
      (node (ref "C31F") (pin "1") (pinfunction "1_1") (pintype "passive"))
      (node (ref "C32F") (pin "1") (pinfunction "1_1") (pintype "passive"))
      (node (ref "C33F") (pin "1") (pinfunction "1_1") (pintype "passive"))
      (node (ref "C35F") (pin "1") (pinfunction "1_1") (pintype "passive"))
      (node (ref "C38F") (pin "1") (pinfunction "1_1") (pintype "passive"))
      (node (ref "C39F") (pin "1") (pinfunction "1_1") (pintype "passive"))
      (node (ref "C40F") (pin "2") (pinfunction "2_2") (pintype "passive"))
      (node (ref "C41F") (pin "1") (pinfunction "1_1") (pintype "passive"))
      (node (ref "C42F") (pin "1") (pinfunction "1_1") (pintype "passive"))
      (node (ref "C43F") (pin "1") (pinfunction "1_1") (pintype "passive"))
      (node (ref "C44F") (pin "1") (pinfunction "1_1") (pintype "passive"))
      (node (ref "C52F") (pin "2") (pinfunction "2_2") (pintype "passive"))
      (node (ref "C53F") (pin "1") (pinfunction "1_1") (pintype "passive"))
      (node (ref "C54F") (pin "1") (pinfunction "1_1") (pintype "passive"))
      (node (ref "C55F") (pin "2") (pinfunction "2_2") (pintype "passive"))
      (node (ref "C56F") (pin "1") (pinfunction "1_1") (pintype "passive"))
      (node (ref "C57F") (pin "1") (pinfunction "1_1") (pintype "passive"))
      (node (ref "C58F") (pin "1") (pinfunction "1_1") (pintype "passive"))
      (node (ref "C59F") (pin "1") (pinfunction "1_1") (pintype "passive"))
      (node (ref "C62F") (pin "1") (pinfunction "1_1") (pintype "passive"))
      (node (ref "C77F") (pin "1") (pinfunction "1_1") (pintype "passive"))
      (node (ref "C78F") (pin "1") (pinfunction "1_1") (pintype "passive"))
      (node (ref "C79F") (pin "1") (pinfunction "1_1") (pintype "passive"))
      (node (ref "C80F") (pin "1") (pinfunction "1_1") (pintype "passive"))
      (node (ref "C81F") (pin "1") (pinfunction "1_1") (pintype "passive"))
      (node (ref "C82F") (pin "1") (pinfunction "1_1") (pintype "passive"))
      (node (ref "C83F") (pin "1") (pinfunction "1_1") (pintype "passive"))
      (node (ref "C84F") (pin "1") (pinfunction "1_1") (pintype "passive"))
      (node (ref "C85F") (pin "1") (pinfunction "1_1") (pintype "passive"))
      (node (ref "C86F") (pin "1") (pinfunction "1_1") (pintype "passive"))
      (node (ref "C87F") (pin "1") (pinfunction "1_1") (pintype "passive"))
      (node (ref "L10F") (pin "1") (pinfunction "1_1") (pintype "passive"))
      (node (ref "L13F") (pin "2") (pinfunction "2_2") (pintype "passive"))
      (node (ref "P10F") (pin "2") (pinfunction "2_2") (pintype "passive"))
      (node (ref "P12F") (pin "18") (pinfunction "18_18") (pintype "passive"))
      (node (ref "R13F") (pin "2") (pinfunction "2_2") (pintype "passive"))
      (node (ref "R15F") (pin "2") (pinfunction "2_2") (pintype "passive"))
      (node (ref "R19F") (pin "1") (pinfunction "1_1") (pintype "passive"))
      (node (ref "R21F") (pin "2") (pinfunction "2_2") (pintype "passive"))
      (node (ref "R22F") (pin "2") (pinfunction "2_2") (pintype "passive"))
      (node (ref "R24F") (pin "2") (pinfunction "2_2") (pintype "passive"))
      (node (ref "R30F") (pin "1") (pinfunction "1_1") (pintype "passive"))
      (node (ref "R31F") (pin "1") (pinfunction "1_1") (pintype "passive"))
      (node (ref "U11F") (pin "D8") (pinfunction "VCCO_0_D8") (pintype "power_in"))
      (node (ref "U11F") (pin "F12") (pinfunction "VCCAUX_F12") (pintype "power_in"))
      (node (ref "U11F") (pin "H12") (pinfunction "VCCAUX_H12") (pintype "power_in"))
      (node (ref "U11F") (pin "K12") (pinfunction "VCCAUX_K12") (pintype "power_in"))
      (node (ref "U11F") (pin "L3") (pinfunction "VCCO_34_L3") (pintype "power_in"))
      (node (ref "U11F") (pin "M12") (pinfunction "VCCAUX_M12") (pintype "power_in"))
      (node (ref "U11F") (pin "N17") (pinfunction "VCCO_14_N17") (pintype "power_in"))
      (node (ref "U11F") (pin "P12") (pinfunction "VCCAUX_P12") (pintype "power_in"))
      (node (ref "U11F") (pin "P4") (pinfunction "VCCO_34_P4") (pintype "power_in"))
      (node (ref "U11F") (pin "T16") (pinfunction "VCCO_14_T16") (pintype "power_in"))
      (node (ref "U11F") (pin "U13") (pinfunction "VCCO_14_U13") (pintype "power_in"))
      (node (ref "U11F") (pin "U5") (pinfunction "VCCO_34_U5") (pintype "power_in"))
      (node (ref "U11F") (pin "V10") (pinfunction "VCCO_0_V10") (pintype "power_in"))
      (node (ref "U13F") (pin "A2") (pinfunction "VOS_A2") (pintype "input"))
      (node (ref "U14F") (pin "2") (pinfunction "VDD_2") (pintype "power_in"))
      (node (ref "U15F") (pin "3") (pinfunction "VDD_3") (pintype "power_in"))
    )
    (net (code "191") (name "P3.3V_A") (class "Default")
      (node (ref "C45F") (pin "1") (pinfunction "1_1") (pintype "passive"))
      (node (ref "C46F") (pin "1") (pinfunction "1_1") (pintype "passive"))
      (node (ref "C47F") (pin "2") (pinfunction "2_2") (pintype "passive"))
      (node (ref "C48F") (pin "1") (pinfunction "1_1") (pintype "passive"))
      (node (ref "C49F") (pin "1") (pinfunction "1_1") (pintype "passive"))
      (node (ref "C50F") (pin "1") (pinfunction "1_1") (pintype "passive"))
      (node (ref "C51F") (pin "1") (pinfunction "1_1") (pintype "passive"))
      (node (ref "C67F") (pin "1") (pinfunction "1_1") (pintype "passive"))
      (node (ref "C68F") (pin "1") (pinfunction "1_1") (pintype "passive"))
      (node (ref "C88F") (pin "1") (pinfunction "1_1") (pintype "passive"))
      (node (ref "C90F") (pin "1") (pinfunction "1_1") (pintype "passive"))
      (node (ref "C91F") (pin "1") (pinfunction "1_1") (pintype "passive"))
      (node (ref "J13F") (pin "4") (pinfunction "VDD_4") (pintype "power_in"))
      (node (ref "P11F") (pin "9") (pinfunction "9_9") (pintype "passive"))
      (node (ref "R25F") (pin "2") (pinfunction "2_2") (pintype "passive"))
      (node (ref "R26F") (pin "2") (pinfunction "2_2") (pintype "passive"))
      (node (ref "R32F") (pin "2") (pinfunction "2_2") (pintype "passive"))
      (node (ref "R33F") (pin "1") (pinfunction "1_1") (pintype "passive"))
      (node (ref "U11F") (pin "C15") (pinfunction "VCCO_15_C15") (pintype "power_in"))
      (node (ref "U11F") (pin "F16") (pinfunction "VCCO_15_F16") (pintype "power_in"))
      (node (ref "U11F") (pin "J17") (pinfunction "VCCO_15_J17") (pintype "power_in"))
    )
    (net (code "192") (name "PACK_P") (class "Default")
      (node (ref "P11F") (pin "4") (pinfunction "4_4") (pintype "passive"))
      (node (ref "P11F") (pin "5") (pinfunction "5_5") (pintype "passive"))
      (node (ref "P11F") (pin "6") (pinfunction "6_6") (pintype "passive"))
    )
    (net (code "193") (name "VBAT") (class "Default")
      (node (ref "C36F") (pin "1") (pinfunction "1_1") (pintype "passive"))
      (node (ref "C66F") (pin "1") (pinfunction "1_1") (pintype "passive"))
      (node (ref "J10F") (pin "1") (pinfunction "1_1") (pintype "passive"))
      (node (ref "Q10F") (pin "4") (pinfunction "S_4") (pintype "passive"))
      (node (ref "R10F") (pin "2") (pinfunction "2_2") (pintype "passive"))
      (node (ref "U18F") (pin "8") (pinfunction "VBACKUP_8") (pintype "power_in"))
    )
    (net (code "194") (name "VBUS") (class "Default")
      (node (ref "C63F") (pin "1") (pinfunction "1_1") (pintype "passive"))
      (node (ref "P12F") (pin "12") (pinfunction "12_12") (pintype "passive"))
      (node (ref "P12F") (pin "13") (pinfunction "13_13") (pintype "passive"))
      (node (ref "P12F") (pin "14") (pinfunction "14_14") (pintype "passive"))
      (node (ref "Q12F") (pin "1") (pinfunction "G_1") (pintype "passive"))
    )
    (net (code "195") (name "VSYS_T") (class "Default")
      (node (ref "C14F") (pin "1") (pinfunction "1_1") (pintype "passive"))
      (node (ref "C15F") (pin "1") (pinfunction "1_1") (pintype "passive"))
      (node (ref "C17F") (pin "1") (pinfunction "1_1") (pintype "passive"))
      (node (ref "J11F") (pin "1") (pinfunction "1_1") (pintype "passive"))
      (node (ref "J12F") (pin "1") (pinfunction "1_1") (pintype "passive"))
      (node (ref "P11F") (pin "19") (pinfunction "19_19") (pintype "passive"))
      (node (ref "Q10F") (pin "2") (pinfunction "D_2") (pintype "passive"))
      (node (ref "Q10F") (pin "3") (pinfunction "D_3") (pintype "passive"))
      (node (ref "R12F") (pin "2") (pinfunction "2_2") (pintype "passive"))
      (node (ref "U12F") (pin "B1") (pinfunction "VIN_B1") (pintype "power_in"))
      (node (ref "U13F") (pin "B1") (pinfunction "VIN_B1") (pintype "power_in"))
    )
    (net (code "196") (name "unconnected-(P12F-Pad10)") (class "Default")
      (node (ref "P12F") (pin "10") (pinfunction "10_10") (pintype "passive"))
    )
    (net (code "197") (name "unconnected-(P12F-Pad15)") (class "Default")
      (node (ref "P12F") (pin "15") (pinfunction "15_15") (pintype "passive"))
    )
    (net (code "198") (name "unconnected-(U11FB-IO_25_14-PadR12)") (class "Default")
      (node (ref "U11F") (pin "R12") (pinfunction "IO_25_14_R12") (pintype "bidirectional"))
    )
    (net (code "199") (name "unconnected-(U11FB-IO_L19P_T3_D26_14-PadP13)") (class "Default")
      (node (ref "U11F") (pin "P13") (pinfunction "IO_L19P_T3_D26_14_P13") (pintype "bidirectional"))
    )
    (net (code "200") (name "unconnected-(U11FB-IO_L22P_T3_D21_14-PadT12)") (class "Default")
      (node (ref "U11F") (pin "T12") (pinfunction "IO_L22P_T3_D21_14_T12") (pintype "bidirectional"))
    )
    (net (code "201") (name "unconnected-(U11FB-IO_L23N_T3_D18_14-PadT11)") (class "Default")
      (node (ref "U11F") (pin "T11") (pinfunction "IO_L23N_T3_D18_14_T11") (pintype "bidirectional"))
    )
    (net (code "202") (name "unconnected-(U11FB-IO_L23P_T3_D19_14-PadR11)") (class "Default")
      (node (ref "U11F") (pin "R11") (pinfunction "IO_L23P_T3_D19_14_R11") (pintype "bidirectional"))
    )
    (net (code "203") (name "unconnected-(U11FB-IO_L24P_T3_D17_14-PadU11)") (class "Default")
      (node (ref "U11F") (pin "U11") (pinfunction "IO_L24P_T3_D17_14_U11") (pintype "bidirectional"))
    )
    (net (code "204") (name "unconnected-(U11FD-IO_25_34-PadP7)") (class "Default")
      (node (ref "U11F") (pin "P7") (pinfunction "IO_25_34_P7") (pintype "bidirectional"))
    )
    (net (code "205") (name "unconnected-(U11FD-IO_L6P_T0_34-PadM6)") (class "Default")
      (node (ref "U11F") (pin "M6") (pinfunction "IO_L6P_T0_34_M6") (pintype "bidirectional"))
    )
    (net (code "206") (name "unconnected-(U11FD-IO_L19P_T3_34-PadP6)") (class "Default")
      (node (ref "U11F") (pin "P6") (pinfunction "IO_L19P_T3_34_P6") (pintype "bidirectional"))
    )
    (net (code "207") (name "unconnected-(U11FD-IO_L23N_T3_34-PadR6)") (class "Default")
      (node (ref "U11F") (pin "R6") (pinfunction "IO_L23N_T3_34_R6") (pintype "bidirectional"))
    )
    (net (code "208") (name "unconnected-(U11FE-NC-PadA2)") (class "Default")
      (node (ref "U11F") (pin "A2") (pinfunction "NC_A2") (pintype "passive"))
    )
    (net (code "209") (name "unconnected-(U11FE-NC-PadA3)") (class "Default")
      (node (ref "U11F") (pin "A3") (pinfunction "NC_A3") (pintype "passive"))
    )
    (net (code "210") (name "unconnected-(U11FE-NC-PadA4)") (class "Default")
      (node (ref "U11F") (pin "A4") (pinfunction "NC_A4") (pintype "passive"))
    )
    (net (code "211") (name "unconnected-(U11FE-NC-PadA5)") (class "Default")
      (node (ref "U11F") (pin "A5") (pinfunction "NC_A5") (pintype "passive"))
    )
    (net (code "212") (name "unconnected-(U11FE-NC-PadA6)") (class "Default")
      (node (ref "U11F") (pin "A6") (pinfunction "NC_A6") (pintype "passive"))
    )
    (net (code "213") (name "unconnected-(U11FE-NC-PadA7)") (class "Default")
      (node (ref "U11F") (pin "A7") (pinfunction "NC_A7") (pintype "passive"))
    )
    (net (code "214") (name "unconnected-(U11FE-NC-PadA8)") (class "Default")
      (node (ref "U11F") (pin "A8") (pinfunction "NC_A8") (pintype "passive"))
    )
    (net (code "215") (name "unconnected-(U11FE-NC-PadA9)") (class "Default")
      (node (ref "U11F") (pin "A9") (pinfunction "NC_A9") (pintype "passive"))
    )
    (net (code "216") (name "unconnected-(U11FE-NC-PadA10)") (class "Default")
      (node (ref "U11F") (pin "A10") (pinfunction "NC_A10") (pintype "passive"))
    )
    (net (code "217") (name "unconnected-(U11FE-NC-PadA11)") (class "Default")
      (node (ref "U11F") (pin "A11") (pinfunction "NC_A11") (pintype "passive"))
    )
    (net (code "218") (name "unconnected-(U11FE-NC-PadB1)") (class "Default")
      (node (ref "U11F") (pin "B1") (pinfunction "NC_B1") (pintype "passive"))
    )
    (net (code "219") (name "unconnected-(U11FE-NC-PadB2)") (class "Default")
      (node (ref "U11F") (pin "B2") (pinfunction "NC_B2") (pintype "passive"))
    )
    (net (code "220") (name "unconnected-(U11FE-NC-PadB3)") (class "Default")
      (node (ref "U11F") (pin "B3") (pinfunction "NC_B3") (pintype "passive"))
    )
    (net (code "221") (name "unconnected-(U11FE-NC-PadB4)") (class "Default")
      (node (ref "U11F") (pin "B4") (pinfunction "NC_B4") (pintype "passive"))
    )
    (net (code "222") (name "unconnected-(U11FE-NC-PadB5)") (class "Default")
      (node (ref "U11F") (pin "B5") (pinfunction "NC_B5") (pintype "passive"))
    )
    (net (code "223") (name "unconnected-(U11FE-NC-PadB6)") (class "Default")
      (node (ref "U11F") (pin "B6") (pinfunction "NC_B6") (pintype "passive"))
    )
    (net (code "224") (name "unconnected-(U11FE-NC-PadB7)") (class "Default")
      (node (ref "U11F") (pin "B7") (pinfunction "NC_B7") (pintype "passive"))
    )
    (net (code "225") (name "unconnected-(U11FE-NC-PadB10)") (class "Default")
      (node (ref "U11F") (pin "B10") (pinfunction "NC_B10") (pintype "passive"))
    )
    (net (code "226") (name "unconnected-(U11FE-NC-PadB11)") (class "Default")
      (node (ref "U11F") (pin "B11") (pinfunction "NC_B11") (pintype "passive"))
    )
    (net (code "227") (name "unconnected-(U11FE-NC-PadB12)") (class "Default")
      (node (ref "U11F") (pin "B12") (pinfunction "NC_B12") (pintype "passive"))
    )
    (net (code "228") (name "unconnected-(U11FE-NC-PadC1)") (class "Default")
      (node (ref "U11F") (pin "C1") (pinfunction "NC_C1") (pintype "passive"))
    )
    (net (code "229") (name "unconnected-(U11FE-NC-PadC2)") (class "Default")
      (node (ref "U11F") (pin "C2") (pinfunction "NC_C2") (pintype "passive"))
    )
    (net (code "230") (name "unconnected-(U11FE-NC-PadC3)") (class "Default")
      (node (ref "U11F") (pin "C3") (pinfunction "NC_C3") (pintype "passive"))
    )
    (net (code "231") (name "unconnected-(U11FE-NC-PadC4)") (class "Default")
      (node (ref "U11F") (pin "C4") (pinfunction "NC_C4") (pintype "passive"))
    )
    (net (code "232") (name "unconnected-(U11FE-NC-PadC5)") (class "Default")
      (node (ref "U11F") (pin "C5") (pinfunction "NC_C5") (pintype "passive"))
    )
    (net (code "233") (name "unconnected-(U11FE-NC-PadC7)") (class "Default")
      (node (ref "U11F") (pin "C7") (pinfunction "NC_C7") (pintype "passive"))
    )
    (net (code "234") (name "unconnected-(U11FE-NC-PadC9)") (class "Default")
      (node (ref "U11F") (pin "C9") (pinfunction "NC_C9") (pintype "passive"))
    )
    (net (code "235") (name "unconnected-(U11FE-NC-PadC10)") (class "Default")
      (node (ref "U11F") (pin "C10") (pinfunction "NC_C10") (pintype "passive"))
    )
    (net (code "236") (name "unconnected-(U11FE-NC-PadC11)") (class "Default")
      (node (ref "U11F") (pin "C11") (pinfunction "NC_C11") (pintype "passive"))
    )
    (net (code "237") (name "unconnected-(U11FE-NC-PadC12)") (class "Default")
      (node (ref "U11F") (pin "C12") (pinfunction "NC_C12") (pintype "passive"))
    )
    (net (code "238") (name "unconnected-(U11FE-NC-PadD1)") (class "Default")
      (node (ref "U11F") (pin "D1") (pinfunction "NC_D1") (pintype "passive"))
    )
    (net (code "239") (name "unconnected-(U11FE-NC-PadD2)") (class "Default")
      (node (ref "U11F") (pin "D2") (pinfunction "NC_D2") (pintype "passive"))
    )
    (net (code "240") (name "unconnected-(U11FE-NC-PadD4)") (class "Default")
      (node (ref "U11F") (pin "D4") (pinfunction "NC_D4") (pintype "passive"))
    )
    (net (code "241") (name "unconnected-(U11FE-NC-PadD5)") (class "Default")
      (node (ref "U11F") (pin "D5") (pinfunction "NC_D5") (pintype "passive"))
    )
    (net (code "242") (name "unconnected-(U11FE-NC-PadD6)") (class "Default")
      (node (ref "U11F") (pin "D6") (pinfunction "NC_D6") (pintype "passive"))
    )
    (net (code "243") (name "unconnected-(U11FE-NC-PadD7)") (class "Default")
      (node (ref "U11F") (pin "D7") (pinfunction "NC_D7") (pintype "passive"))
    )
    (net (code "244") (name "unconnected-(U11FE-NC-PadD10)") (class "Default")
      (node (ref "U11F") (pin "D10") (pinfunction "NC_D10") (pintype "passive"))
    )
    (net (code "245") (name "unconnected-(U11FE-NC-PadD11)") (class "Default")
      (node (ref "U11F") (pin "D11") (pinfunction "NC_D11") (pintype "passive"))
    )
    (net (code "246") (name "unconnected-(U11FE-NC-PadE1)") (class "Default")
      (node (ref "U11F") (pin "E1") (pinfunction "NC_E1") (pintype "passive"))
    )
    (net (code "247") (name "unconnected-(U11FE-NC-PadE2)") (class "Default")
      (node (ref "U11F") (pin "E2") (pinfunction "NC_E2") (pintype "passive"))
    )
    (net (code "248") (name "unconnected-(U11FE-NC-PadE3)") (class "Default")
      (node (ref "U11F") (pin "E3") (pinfunction "NC_E3") (pintype "passive"))
    )
    (net (code "249") (name "unconnected-(U11FE-NC-PadE4)") (class "Default")
      (node (ref "U11F") (pin "E4") (pinfunction "NC_E4") (pintype "passive"))
    )
    (net (code "250") (name "unconnected-(U11FE-NC-PadE5)") (class "Default")
      (node (ref "U11F") (pin "E5") (pinfunction "NC_E5") (pintype "passive"))
    )
    (net (code "251") (name "unconnected-(U11FE-NC-PadE6)") (class "Default")
      (node (ref "U11F") (pin "E6") (pinfunction "NC_E6") (pintype "passive"))
    )
    (net (code "252") (name "unconnected-(U11FE-NC-PadF1)") (class "Default")
      (node (ref "U11F") (pin "F1") (pinfunction "NC_F1") (pintype "passive"))
    )
    (net (code "253") (name "unconnected-(U11FE-NC-PadF2)") (class "Default")
      (node (ref "U11F") (pin "F2") (pinfunction "NC_F2") (pintype "passive"))
    )
    (net (code "254") (name "unconnected-(U11FE-NC-PadF3)") (class "Default")
      (node (ref "U11F") (pin "F3") (pinfunction "NC_F3") (pintype "passive"))
    )
    (net (code "255") (name "unconnected-(U11FE-NC-PadF4)") (class "Default")
      (node (ref "U11F") (pin "F4") (pinfunction "NC_F4") (pintype "passive"))
    )
    (net (code "256") (name "unconnected-(U11FE-NC-PadF5)") (class "Default")
      (node (ref "U11F") (pin "F5") (pinfunction "NC_F5") (pintype "passive"))
    )
    (net (code "257") (name "unconnected-(U11FE-NC-PadF6)") (class "Default")
      (node (ref "U11F") (pin "F6") (pinfunction "NC_F6") (pintype "passive"))
    )
    (net (code "258") (name "unconnected-(U11FE-NC-PadG1)") (class "Default")
      (node (ref "U11F") (pin "G1") (pinfunction "NC_G1") (pintype "passive"))
    )
    (net (code "259") (name "unconnected-(U11FE-NC-PadG2)") (class "Default")
      (node (ref "U11F") (pin "G2") (pinfunction "NC_G2") (pintype "passive"))
    )
    (net (code "260") (name "unconnected-(U11FE-NC-PadG3)") (class "Default")
      (node (ref "U11F") (pin "G3") (pinfunction "NC_G3") (pintype "passive"))
    )
    (net (code "261") (name "unconnected-(U11FE-NC-PadG5)") (class "Default")
      (node (ref "U11F") (pin "G5") (pinfunction "NC_G5") (pintype "passive"))
    )
    (net (code "262") (name "unconnected-(U11FE-NC-PadG6)") (class "Default")
      (node (ref "U11F") (pin "G6") (pinfunction "NC_G6") (pintype "passive"))
    )
    (net (code "263") (name "unconnected-(U11FE-NC-PadH2)") (class "Default")
      (node (ref "U11F") (pin "H2") (pinfunction "NC_H2") (pintype "passive"))
    )
    (net (code "264") (name "unconnected-(U11FE-NC-PadH3)") (class "Default")
      (node (ref "U11F") (pin "H3") (pinfunction "NC_H3") (pintype "passive"))
    )
    (net (code "265") (name "unconnected-(U11FE-NC-PadH4)") (class "Default")
      (node (ref "U11F") (pin "H4") (pinfunction "NC_H4") (pintype "passive"))
    )
    (net (code "266") (name "unconnected-(U11FE-NC-PadH5)") (class "Default")
      (node (ref "U11F") (pin "H5") (pinfunction "NC_H5") (pintype "passive"))
    )
    (net (code "267") (name "unconnected-(U11FE-NC-PadH6)") (class "Default")
      (node (ref "U11F") (pin "H6") (pinfunction "NC_H6") (pintype "passive"))
    )
    (net (code "268") (name "unconnected-(U11FE-NC-PadJ1)") (class "Default")
      (node (ref "U11F") (pin "J1") (pinfunction "NC_J1") (pintype "passive"))
    )
    (net (code "269") (name "unconnected-(U11FE-NC-PadJ2)") (class "Default")
      (node (ref "U11F") (pin "J2") (pinfunction "NC_J2") (pintype "passive"))
    )
    (net (code "270") (name "unconnected-(U11FE-NC-PadJ3)") (class "Default")
      (node (ref "U11F") (pin "J3") (pinfunction "NC_J3") (pintype "passive"))
    )
    (net (code "271") (name "unconnected-(U11FE-NC-PadJ4)") (class "Default")
      (node (ref "U11F") (pin "J4") (pinfunction "NC_J4") (pintype "passive"))
    )
    (net (code "272") (name "unconnected-(U11FE-NC-PadJ5)") (class "Default")
      (node (ref "U11F") (pin "J5") (pinfunction "NC_J5") (pintype "passive"))
    )
    (net (code "273") (name "unconnected-(U18F-CLKOUT-Pad5)") (class "Default")
      (node (ref "U18F") (pin "5") (pinfunction "CLKOUT_5") (pintype "open_collector"))
    )
  )
)
